# RD2166-v1_0_0.net
KiCad netlist of a schematic drawn in EAGLE
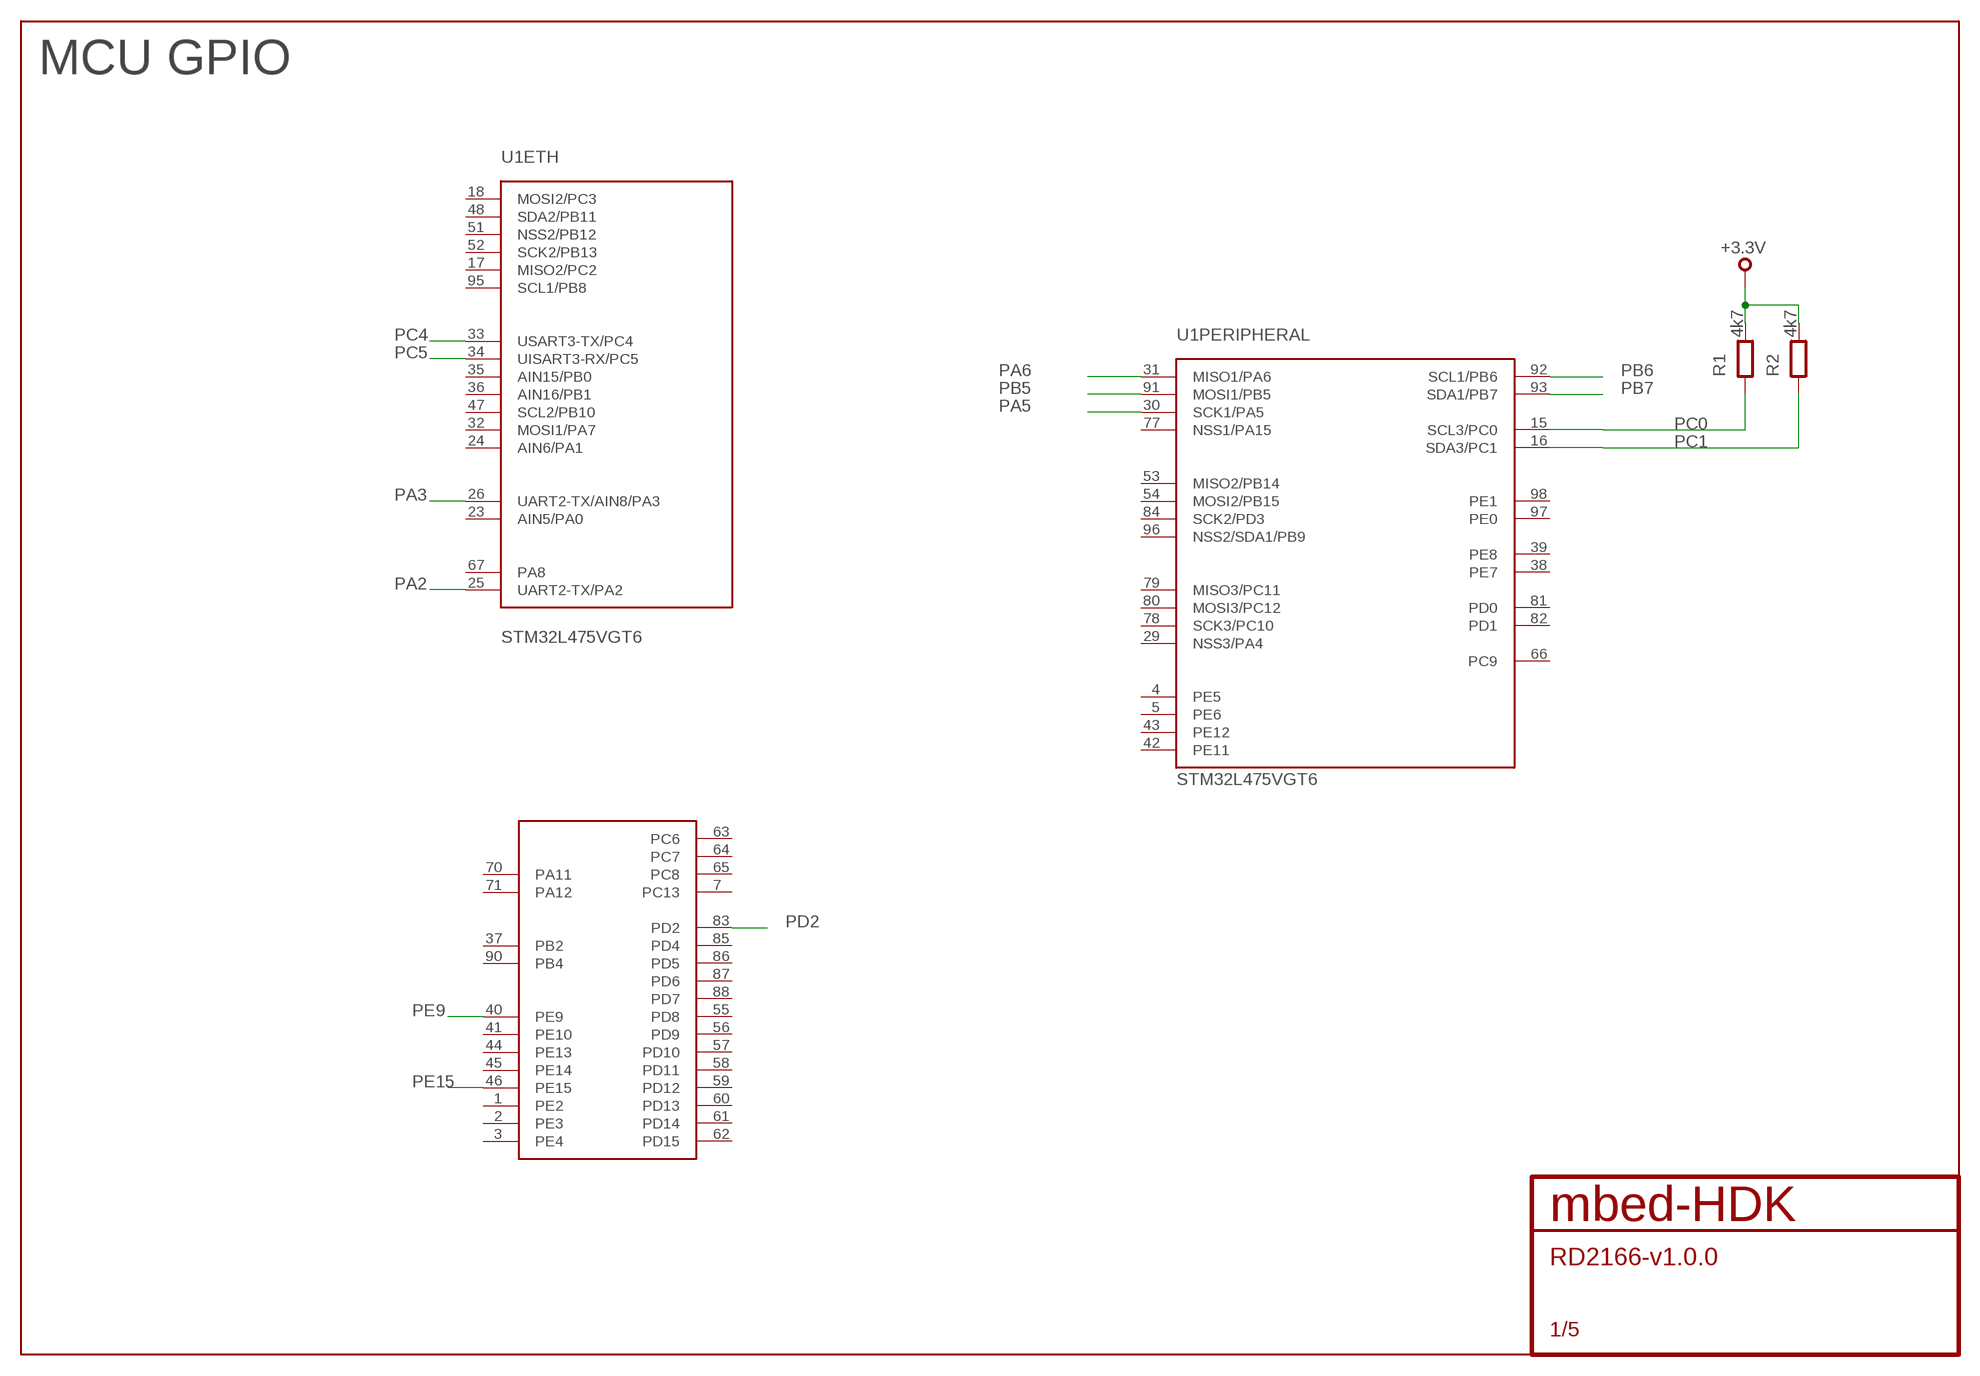
[diagram p0: schematic, sheet 1]
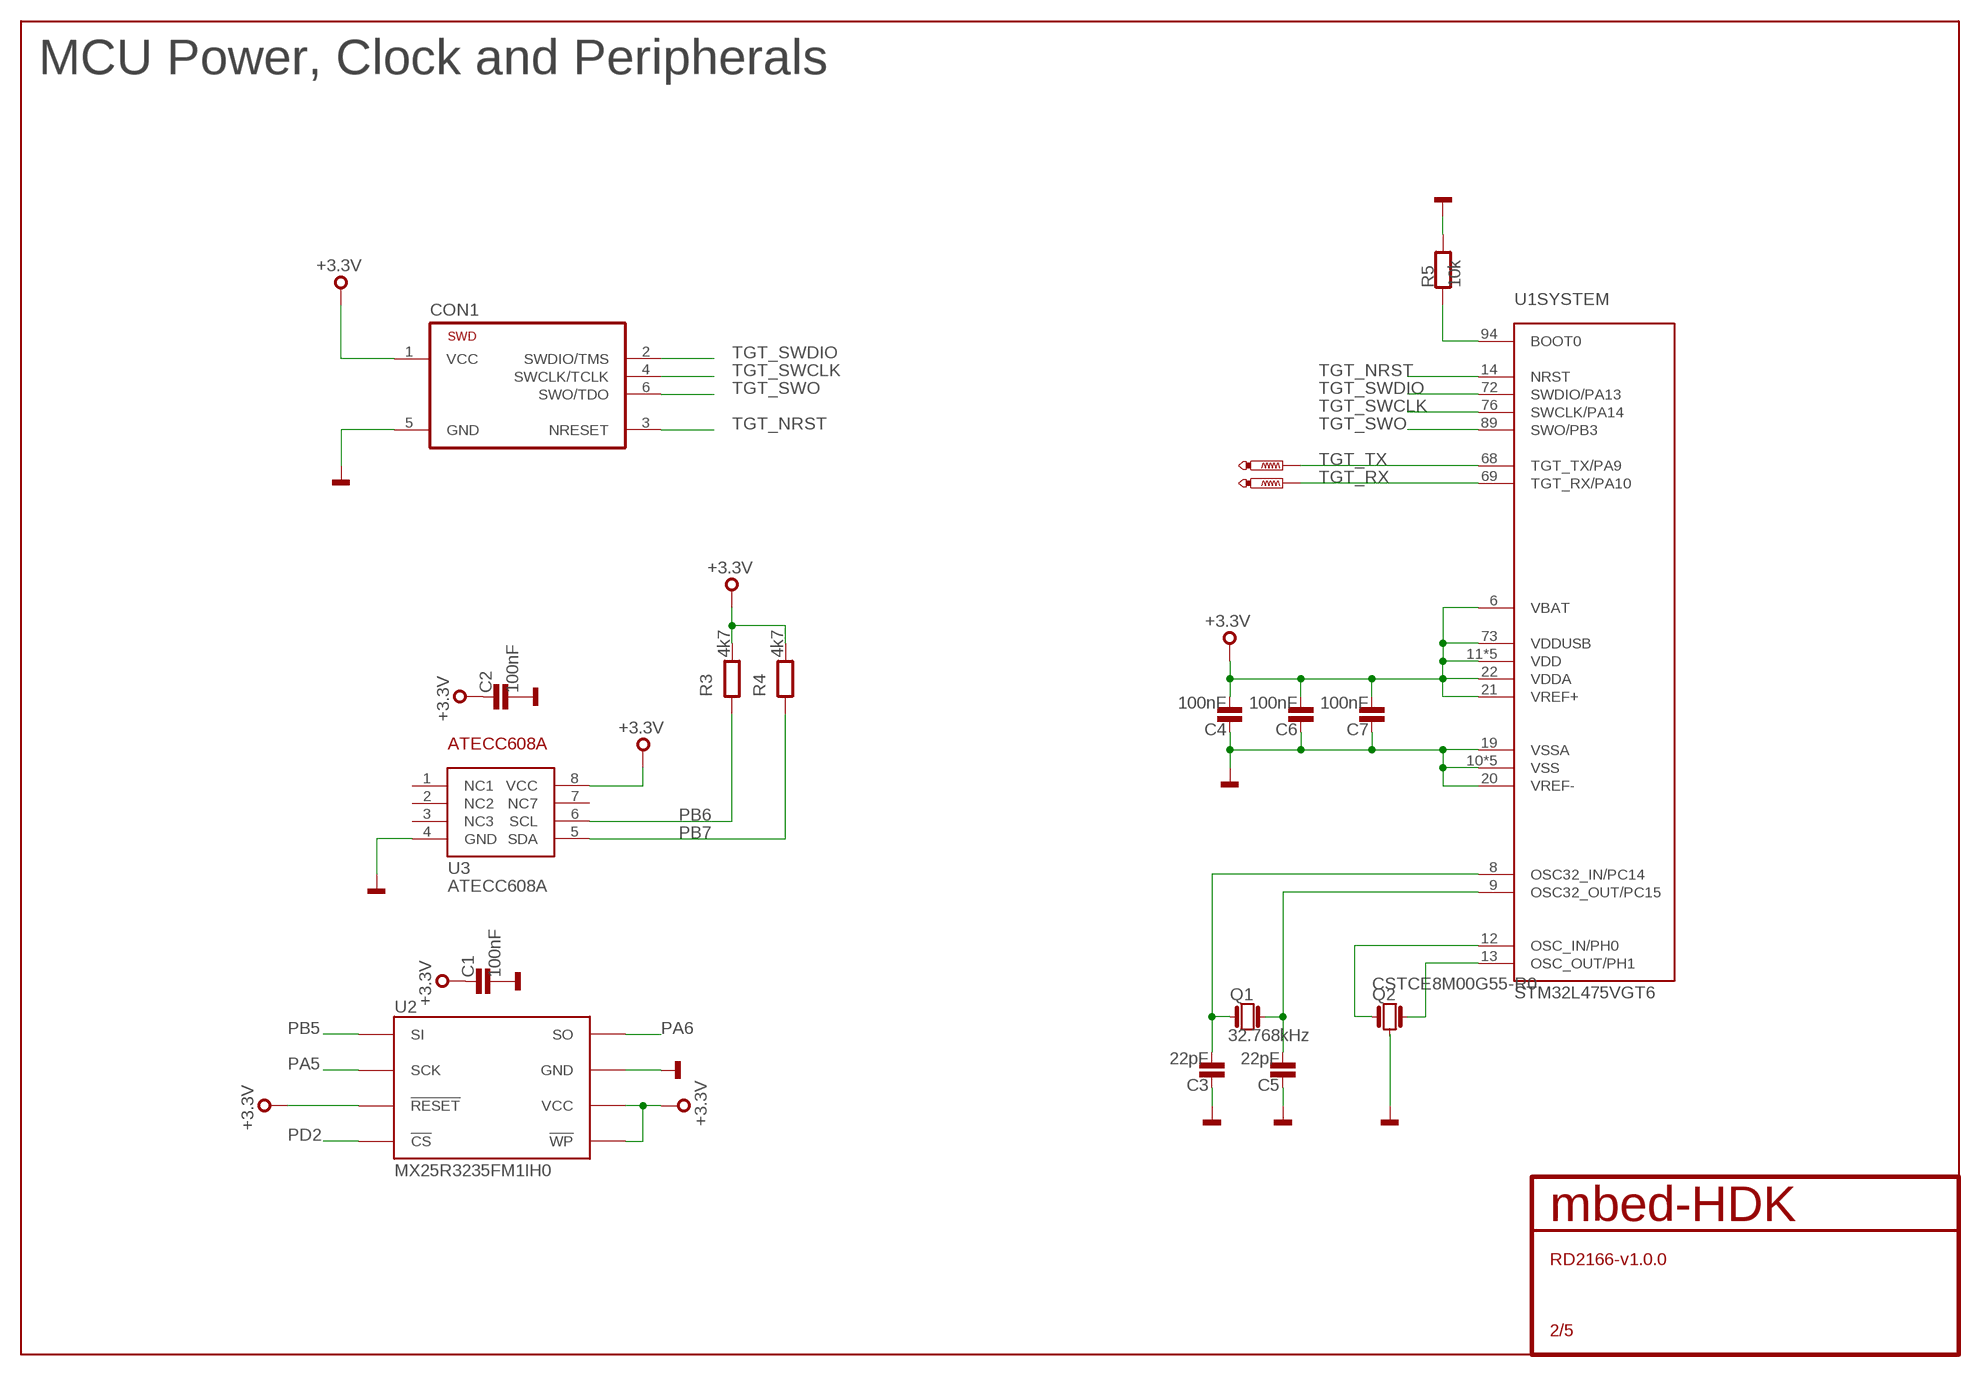
[diagram p1: schematic, sheet 2]
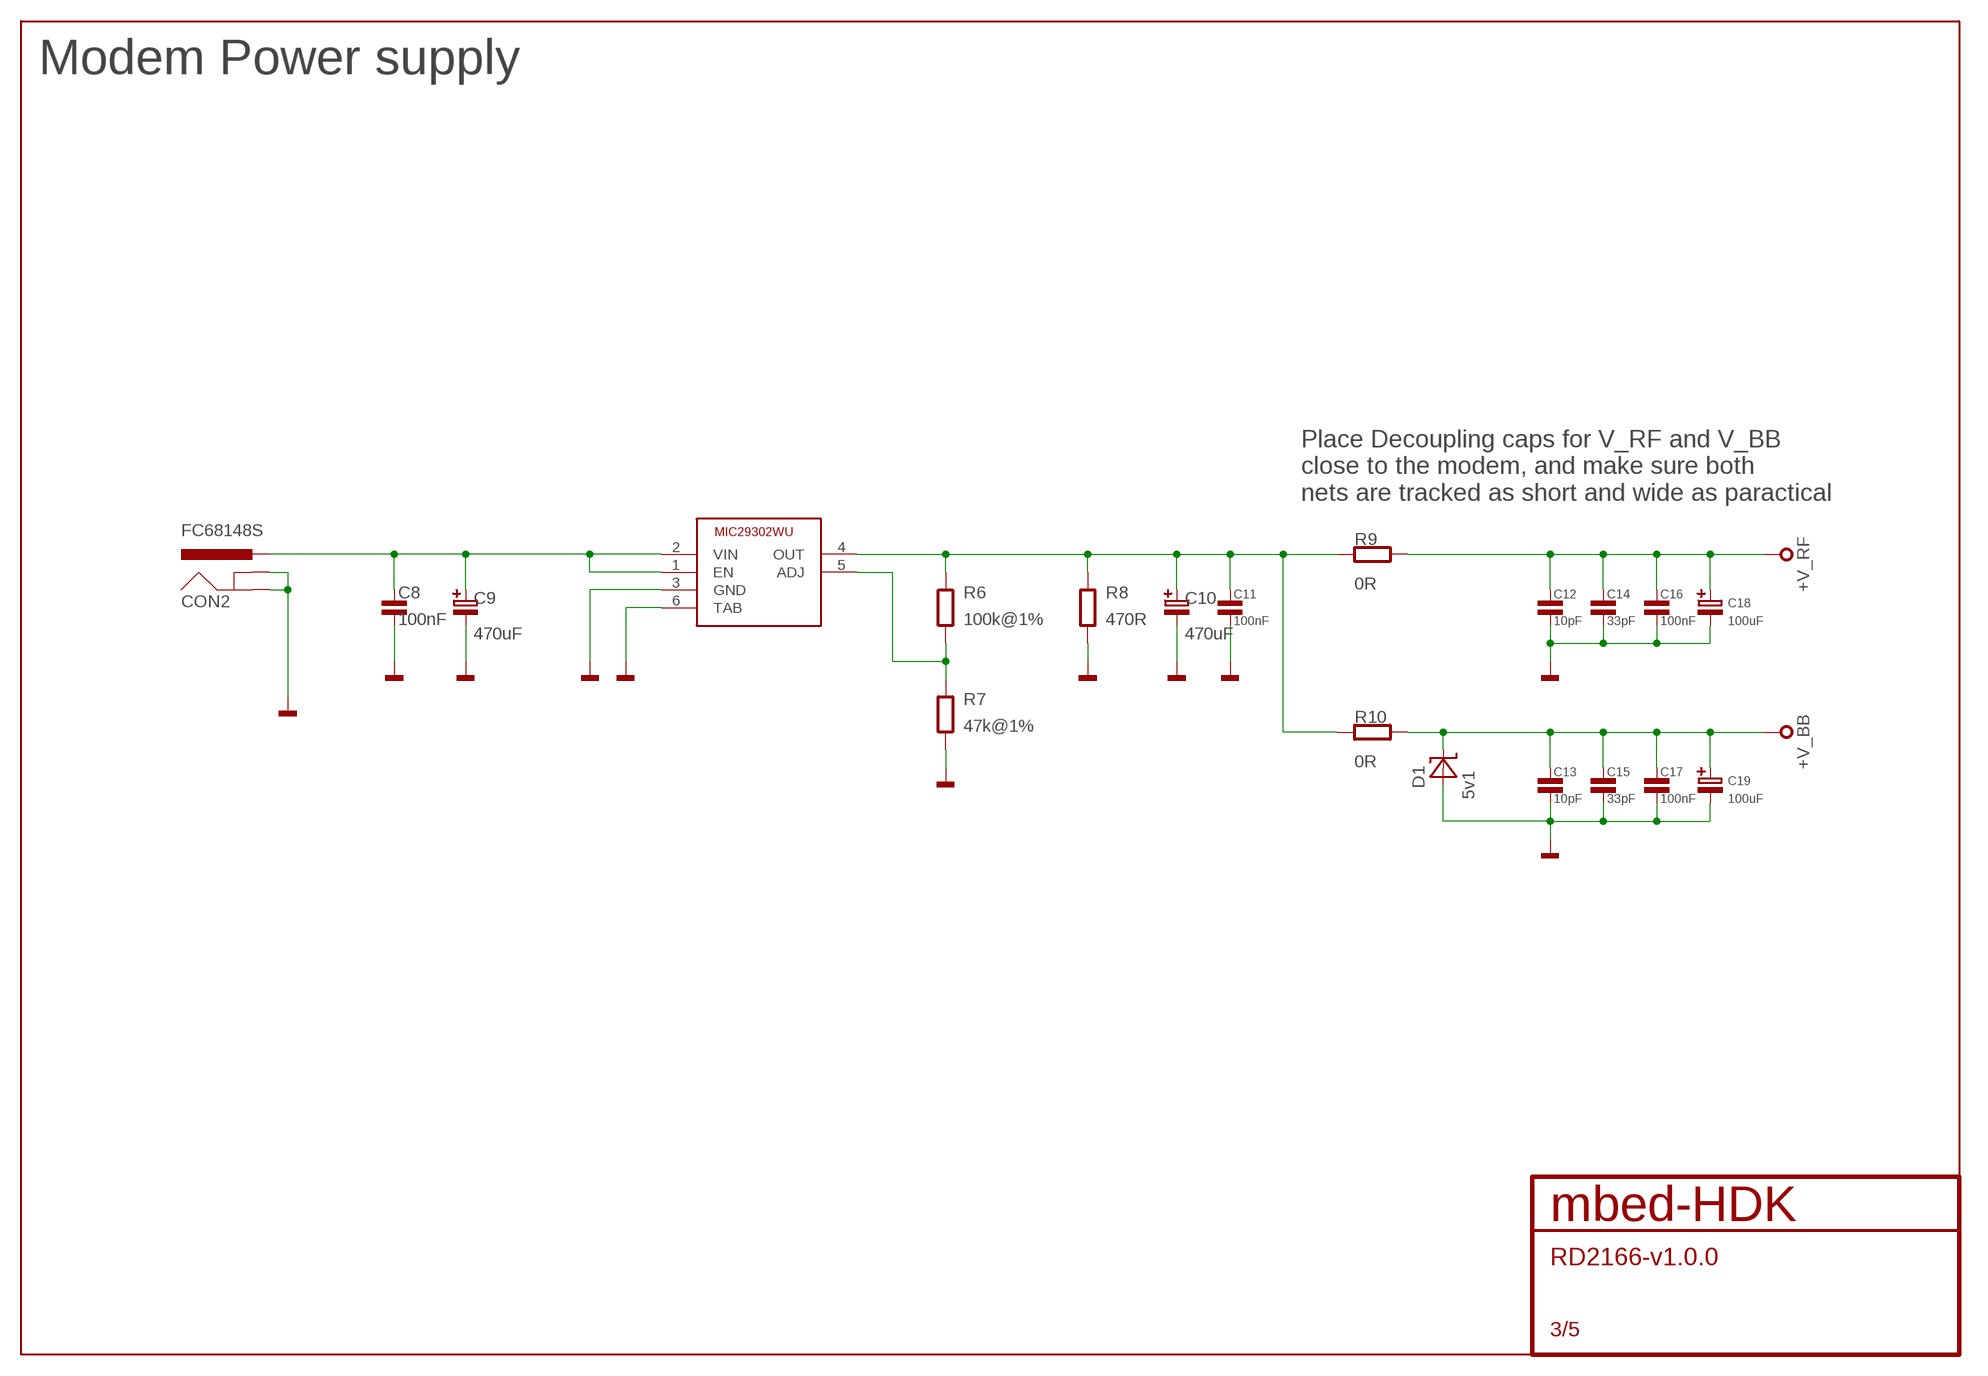
[diagram p2: schematic, sheet 3]
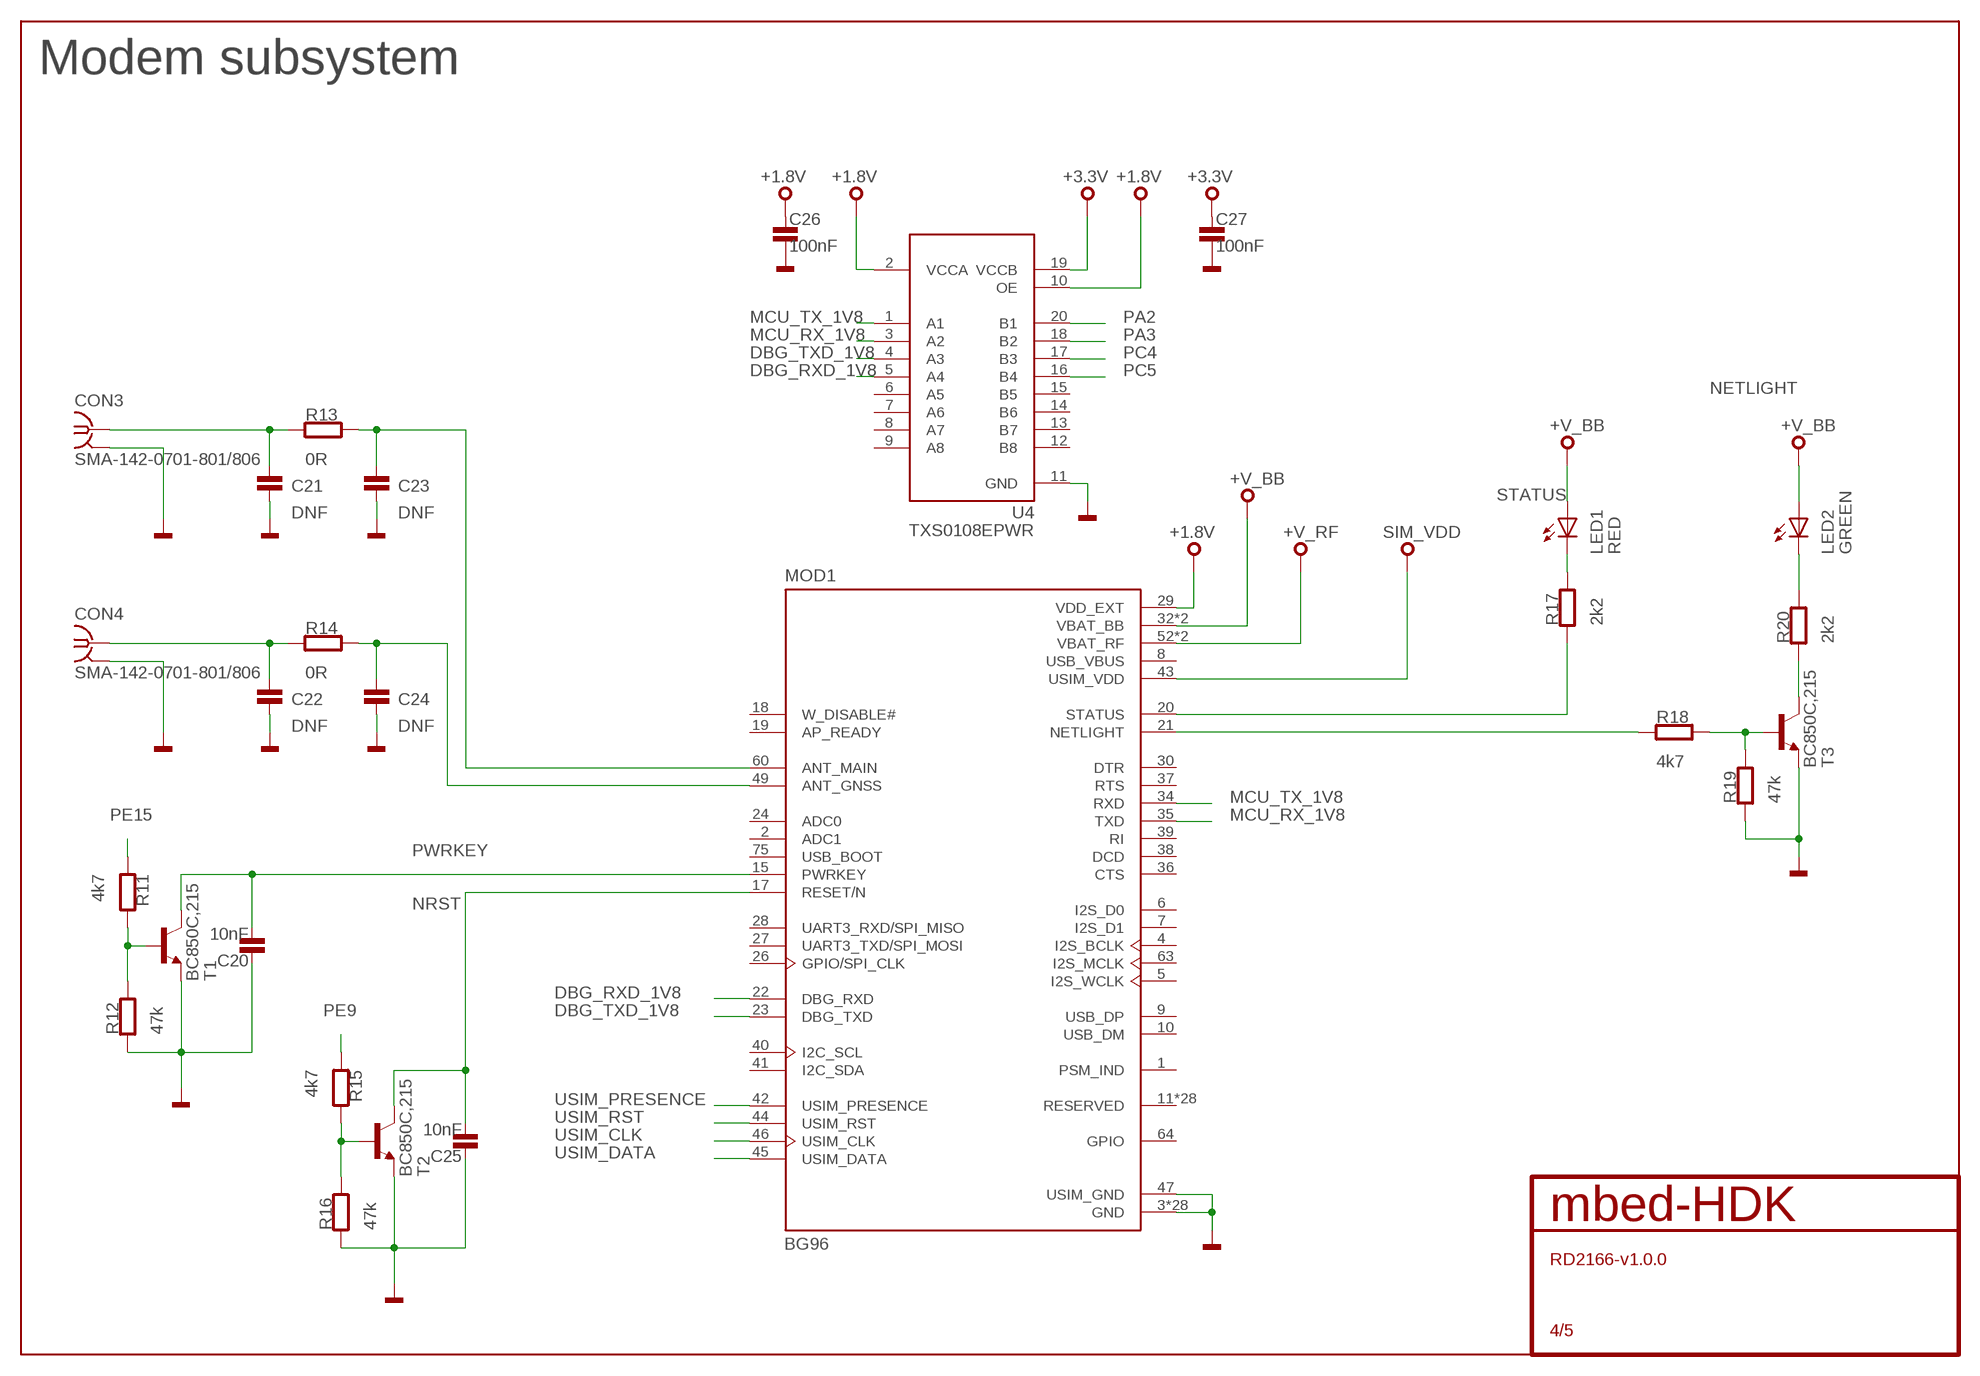
[diagram p3: schematic, sheet 4]
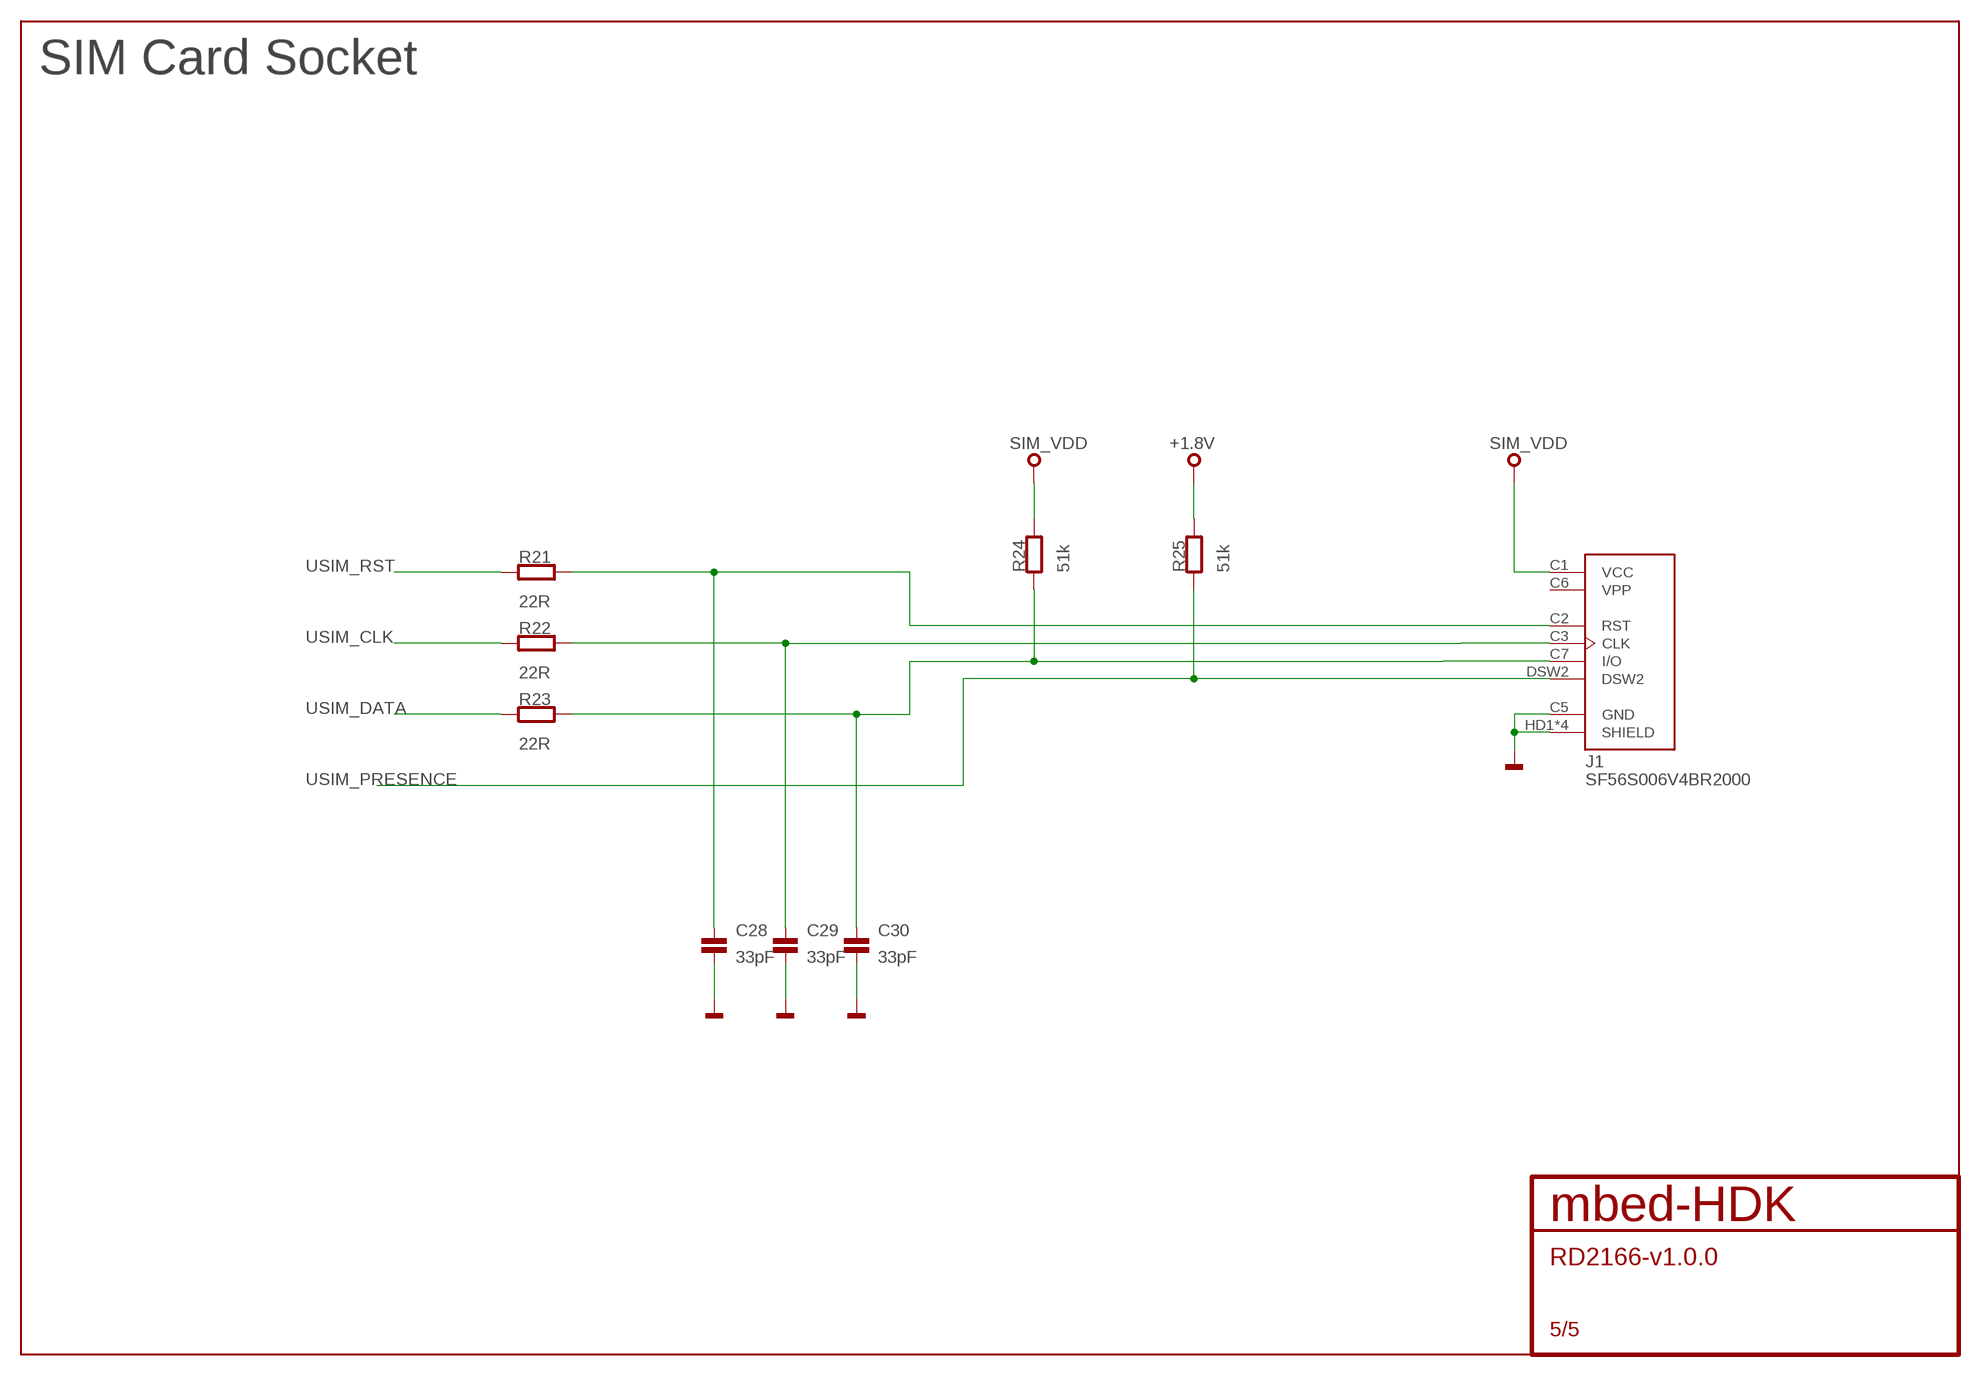
[diagram p4: schematic, sheet 5]

(export (version "E")
  (design (tool "Eeschema 10.0.6"))
  (components
    (comp (ref "C28")
      (value "33pF")
      (footprint "eagle-import:0603")
      (libsource (lib "eagle-import") (part "C0603"))
    )
    (comp (ref "C29")
      (value "33pF")
      (footprint "eagle-import:0603")
      (libsource (lib "eagle-import") (part "C0603"))
    )
    (comp (ref "C30")
      (value "33pF")
      (footprint "eagle-import:0603")
      (libsource (lib "eagle-import") (part "C0603"))
    )
    (comp (ref "J1")
      (value "SF56S006V4BR2000")
      (footprint "eagle-import:JAE_SF56S006V4BR2000")
      (fields (field (name "DIGI-KEY_PART_NUMBER") "670-2834-1-ND") (field (name "MF") "JAE Electronics"))
      (libsource (lib "eagle-import") (part "SF56S006V4BR2000"))
    )
    (comp (ref "R21")
      (value "22R")
      (footprint "eagle-import:0603")
      (libsource (lib "eagle-import") (part "R0603"))
    )
    (comp (ref "R22")
      (value "22R")
      (footprint "eagle-import:0603")
      (libsource (lib "eagle-import") (part "R0603"))
    )
    (comp (ref "R23")
      (value "22R")
      (footprint "eagle-import:0603")
      (libsource (lib "eagle-import") (part "R0603"))
    )
    (comp (ref "R24")
      (value "51k")
      (footprint "eagle-import:0603")
      (libsource (lib "eagle-import") (part "R0603"))
    )
    (comp (ref "R25")
      (value "51k")
      (footprint "eagle-import:0603")
      (libsource (lib "eagle-import") (part "R0603"))
    )
    (comp (ref "C20")
      (value "10nF")
      (footprint "eagle-import:0603")
      (libsource (lib "eagle-import") (part "C0603"))
    )
    (comp (ref "C21")
      (value "DNF")
      (footprint "eagle-import:0603")
      (libsource (lib "eagle-import") (part "C0603"))
    )
    (comp (ref "C22")
      (value "DNF")
      (footprint "eagle-import:0603")
      (libsource (lib "eagle-import") (part "C0603"))
    )
    (comp (ref "C23")
      (value "DNF")
      (footprint "eagle-import:0603")
      (libsource (lib "eagle-import") (part "C0603"))
    )
    (comp (ref "C24")
      (value "DNF")
      (footprint "eagle-import:0603")
      (libsource (lib "eagle-import") (part "C0603"))
    )
    (comp (ref "C25")
      (value "10nF")
      (footprint "eagle-import:0603")
      (libsource (lib "eagle-import") (part "C0603"))
    )
    (comp (ref "C26")
      (value "100nF")
      (footprint "eagle-import:0603")
      (libsource (lib "eagle-import") (part "C0603"))
    )
    (comp (ref "C27")
      (value "100nF")
      (footprint "eagle-import:0603")
      (libsource (lib "eagle-import") (part "C0603"))
    )
    (comp (ref "CON3")
      (value "SMA-142-0701-801/806")
      (footprint "eagle-import:J502-ND-142-0701-801_806")
      (fields (field (name "MF") "JOHNSON COMPONENTS") (field (name "MPN") "142-0701-801"))
      (libsource (lib "eagle-import") (part "SMA-142-0701-801/806"))
    )
    (comp (ref "CON4")
      (value "SMA-142-0701-801/806")
      (footprint "eagle-import:J502-ND-142-0701-801_806")
      (fields (field (name "MF") "JOHNSON COMPONENTS") (field (name "MPN") "142-0701-801"))
      (libsource (lib "eagle-import") (part "SMA-142-0701-801/806"))
    )
    (comp (ref "LED1")
      (value "RED")
      (footprint "eagle-import:CHIPLED_0603")
      (libsource (lib "eagle-import") (part "LED0603"))
    )
    (comp (ref "LED2")
      (value "GREEN")
      (footprint "eagle-import:CHIPLED_0603")
      (libsource (lib "eagle-import") (part "LED0603"))
    )
    (comp (ref "MOD1")
      (value "BG96")
      (footprint "eagle-import:LTE_MODULE_BG96")
      (fields (field (name "MF") "Quectel"))
      (libsource (lib "eagle-import") (part "BG96"))
    )
    (comp (ref "R11")
      (value "4k7")
      (footprint "eagle-import:0603")
      (libsource (lib "eagle-import") (part "R0603"))
    )
    (comp (ref "R12")
      (value "47k")
      (footprint "eagle-import:0603")
      (libsource (lib "eagle-import") (part "R0603"))
    )
    (comp (ref "R13")
      (value "0R")
      (footprint "eagle-import:0603")
      (libsource (lib "eagle-import") (part "R0603"))
    )
    (comp (ref "R14")
      (value "0R")
      (footprint "eagle-import:0603")
      (libsource (lib "eagle-import") (part "R0603"))
    )
    (comp (ref "R15")
      (value "4k7")
      (footprint "eagle-import:0603")
      (libsource (lib "eagle-import") (part "R0603"))
    )
    (comp (ref "R16")
      (value "47k")
      (footprint "eagle-import:0603")
      (libsource (lib "eagle-import") (part "R0603"))
    )
    (comp (ref "R17")
      (value "2k2")
      (footprint "eagle-import:0603")
      (libsource (lib "eagle-import") (part "R0603"))
    )
    (comp (ref "R18")
      (value "4k7")
      (footprint "eagle-import:0603")
      (libsource (lib "eagle-import") (part "R0603"))
    )
    (comp (ref "R19")
      (value "47k")
      (footprint "eagle-import:0603")
      (libsource (lib "eagle-import") (part "R0603"))
    )
    (comp (ref "R20")
      (value "2k2")
      (footprint "eagle-import:0603")
      (libsource (lib "eagle-import") (part "R0603"))
    )
    (comp (ref "T1")
      (value "BC850C,215")
      (footprint "eagle-import:SOT23-3")
      (fields (field (name "MF") "NXP Semiconductors"))
      (libsource (lib "eagle-import") (part "BC850C,215"))
    )
    (comp (ref "T2")
      (value "BC850C,215")
      (footprint "eagle-import:SOT23-3")
      (fields (field (name "MF") "NXP Semiconductors"))
      (libsource (lib "eagle-import") (part "BC850C,215"))
    )
    (comp (ref "T3")
      (value "BC850C,215")
      (footprint "eagle-import:SOT23-3")
      (fields (field (name "MF") "NXP Semiconductors"))
      (libsource (lib "eagle-import") (part "BC850C,215"))
    )
    (comp (ref "U4")
      (value "TXS0108EPWR")
      (footprint "eagle-import:TSSOP-20")
      (fields (field (name "MF") "Texas Instruments"))
      (libsource (lib "eagle-import") (part "TXS0108EPWR"))
    )
    (comp (ref "R1")
      (value "4k7")
      (footprint "eagle-import:0603")
      (libsource (lib "eagle-import") (part "R0603"))
    )
    (comp (ref "R2")
      (value "4k7")
      (footprint "eagle-import:0603")
      (libsource (lib "eagle-import") (part "R0603"))
    )
    (comp (ref "U1")
      (value "STM32L475VGT6")
      (footprint "eagle-import:QFP50P1600X1600X160-100N")
      (libsource (lib "eagle-import") (part "STM32L475VGT6"))
    )
    (comp (ref "C8")
      (value "100nF")
      (footprint "eagle-import:0603")
      (libsource (lib "eagle-import") (part "C0603"))
    )
    (comp (ref "C9")
      (value "470uF")
      (footprint "eagle-import:PANASONIC_G")
      (libsource (lib "eagle-import") (part "C-POL_G"))
    )
    (comp (ref "C10")
      (value "470uF")
      (footprint "eagle-import:PANASONIC_G")
      (libsource (lib "eagle-import") (part "C-POL_G"))
    )
    (comp (ref "C11")
      (value "100nF")
      (footprint "eagle-import:0603")
      (libsource (lib "eagle-import") (part "C0603"))
    )
    (comp (ref "C12")
      (value "10pF")
      (footprint "eagle-import:0603")
      (libsource (lib "eagle-import") (part "C0603"))
    )
    (comp (ref "C13")
      (value "10pF")
      (footprint "eagle-import:0603")
      (libsource (lib "eagle-import") (part "C0603"))
    )
    (comp (ref "C14")
      (value "33pF")
      (footprint "eagle-import:0603")
      (libsource (lib "eagle-import") (part "C0603"))
    )
    (comp (ref "C15")
      (value "33pF")
      (footprint "eagle-import:0603")
      (libsource (lib "eagle-import") (part "C0603"))
    )
    (comp (ref "C16")
      (value "100nF")
      (footprint "eagle-import:0603")
      (libsource (lib "eagle-import") (part "C0603"))
    )
    (comp (ref "C17")
      (value "100nF")
      (footprint "eagle-import:0603")
      (libsource (lib "eagle-import") (part "C0603"))
    )
    (comp (ref "C18")
      (value "100uF")
      (footprint "eagle-import:SMC_A")
      (libsource (lib "eagle-import") (part "C-POLA"))
    )
    (comp (ref "C19")
      (value "100uF")
      (footprint "eagle-import:SMC_A")
      (libsource (lib "eagle-import") (part "C-POLA"))
    )
    (comp (ref "CON2")
      (value "FC68148S")
      (footprint "eagle-import:FC68148S")
      (fields (field (name "MF") "Cliff"))
      (libsource (lib "eagle-import") (part "FC68148S"))
    )
    (comp (ref "D1")
      (value "5v1")
      (footprint "eagle-import:SOD123")
      (libsource (lib "eagle-import") (part "DIODE-ZENER"))
    )
    (comp (ref "IC1")
      (value "MIC29302WU")
      (footprint "eagle-import:TO263-5")
      (fields (field (name "MF") "Microchip"))
      (libsource (lib "eagle-import") (part "MIC29302WU"))
    )
    (comp (ref "R6")
      (value "100k@1%")
      (footprint "eagle-import:0603")
      (libsource (lib "eagle-import") (part "R0603"))
    )
    (comp (ref "R7")
      (value "47k@1%")
      (footprint "eagle-import:0603")
      (libsource (lib "eagle-import") (part "R0603"))
    )
    (comp (ref "R8")
      (value "470R")
      (footprint "eagle-import:0603")
      (libsource (lib "eagle-import") (part "R0603"))
    )
    (comp (ref "R9")
      (value "0R")
      (footprint "eagle-import:0603")
      (libsource (lib "eagle-import") (part "R0603"))
    )
    (comp (ref "R10")
      (value "0R")
      (footprint "eagle-import:0603")
      (libsource (lib "eagle-import") (part "R0603"))
    )
    (comp (ref "C1")
      (value "100nF")
      (footprint "eagle-import:0603")
      (libsource (lib "eagle-import") (part "C0603"))
    )
    (comp (ref "C2")
      (value "100nF")
      (footprint "eagle-import:0603")
      (libsource (lib "eagle-import") (part "C0603"))
    )
    (comp (ref "C3")
      (value "22pF")
      (footprint "eagle-import:0603")
      (libsource (lib "eagle-import") (part "C0603"))
    )
    (comp (ref "C4")
      (value "100nF")
      (footprint "eagle-import:0603")
      (libsource (lib "eagle-import") (part "C0603"))
    )
    (comp (ref "C5")
      (value "22pF")
      (footprint "eagle-import:0603")
      (libsource (lib "eagle-import") (part "C0603"))
    )
    (comp (ref "C6")
      (value "100nF")
      (footprint "eagle-import:0603")
      (libsource (lib "eagle-import") (part "C0603"))
    )
    (comp (ref "C7")
      (value "100nF")
      (footprint "eagle-import:0603")
      (libsource (lib "eagle-import") (part "C0603"))
    )
    (comp (ref "CON1")
      (value "TC2030-CTX-NL")
      (footprint "eagle-import:TC2030-CTX-NL")
      (libsource (lib "eagle-import") (part "TC2030-CTX-NL"))
    )
    (comp (ref "Q1")
      (value "32.768kHz")
      (footprint "eagle-import:FC135")
      (libsource (lib "eagle-import") (part "GENERIC-CRYSTAL_FC135"))
    )
    (comp (ref "Q2")
      (value "CSTCE8M00G55-R0")
      (footprint "eagle-import:CSTCE8M00G55-R0")
      (fields (field (name "MF") "Murata"))
      (libsource (lib "eagle-import") (part "CSTCE8M00G55-R0"))
    )
    (comp (ref "R3")
      (value "4k7")
      (footprint "eagle-import:0603")
      (libsource (lib "eagle-import") (part "R0603"))
    )
    (comp (ref "R4")
      (value "4k7")
      (footprint "eagle-import:0603")
      (libsource (lib "eagle-import") (part "R0603"))
    )
    (comp (ref "R5")
      (value "10k")
      (footprint "eagle-import:0603")
      (libsource (lib "eagle-import") (part "R0603"))
    )
    (comp (ref "TP1")
      (value "PTR1TP06R")
      (footprint "eagle-import:TP06R")
      (libsource (lib "eagle-import") (part "PTR1TP06R"))
    )
    (comp (ref "TP2")
      (value "PTR1TP06R")
      (footprint "eagle-import:TP06R")
      (libsource (lib "eagle-import") (part "PTR1TP06R"))
    )
    (comp (ref "U2")
      (value "MX25R3235FM1IH0")
      (footprint "eagle-import:SO8")
      (fields (field (name "MF") "Macronix"))
      (libsource (lib "eagle-import") (part "MX25R3235FM1IH0"))
    )
    (comp (ref "U3")
      (value "ATECC608A")
      (footprint "eagle-import:SO8")
      (libsource (lib "eagle-import") (part "ATECC608A"))
    )
  )
  (nets
    (net (code "1") (name "+1.8V") (class "Default")
      (node (ref "C26") (pin "1") (pinfunction "P$1_1") (pintype "passive"))
      (node (ref "MOD1") (pin "29") (pinfunction "VDD_EXT_29") (pintype "power_in"))
      (node (ref "R25") (pin "2") (pinfunction "P$2_2") (pintype "passive"))
      (node (ref "U4") (pin "10") (pinfunction "OE_10") (pintype "bidirectional"))
      (node (ref "U4") (pin "2") (pinfunction "VCCA_2") (pintype "bidirectional"))
    )
    (net (code "2") (name "+3.3V") (class "Default")
      (node (ref "C1") (pin "1") (pinfunction "P$1_1") (pintype "passive"))
      (node (ref "C2") (pin "1") (pinfunction "P$1_1") (pintype "passive"))
      (node (ref "C27") (pin "1") (pinfunction "P$1_1") (pintype "passive"))
      (node (ref "C4") (pin "2") (pinfunction "P$2_2") (pintype "passive"))
      (node (ref "C6") (pin "2") (pinfunction "P$2_2") (pintype "passive"))
      (node (ref "C7") (pin "2") (pinfunction "P$2_2") (pintype "passive"))
      (node (ref "CON1") (pin "1") (pinfunction "VCC_1") (pintype "passive"))
      (node (ref "R1") (pin "2") (pinfunction "P$2_2") (pintype "passive"))
      (node (ref "R2") (pin "2") (pinfunction "P$2_2") (pintype "passive"))
      (node (ref "R3") (pin "2") (pinfunction "P$2_2") (pintype "passive"))
      (node (ref "R4") (pin "2") (pinfunction "P$2_2") (pintype "passive"))
      (node (ref "U1") (pin "100") (pinfunction "VDD_100") (pintype "power_in"))
      (node (ref "U1") (pin "11") (pinfunction "VDD_11") (pintype "power_in"))
      (node (ref "U1") (pin "21") (pinfunction "VREF+_21") (pintype "power_in"))
      (node (ref "U1") (pin "22") (pinfunction "VDDA_22") (pintype "power_in"))
      (node (ref "U1") (pin "28") (pinfunction "VDD_28") (pintype "power_in"))
      (node (ref "U1") (pin "50") (pinfunction "VDD_50") (pintype "power_in"))
      (node (ref "U1") (pin "6") (pinfunction "VBAT_6") (pintype "power_in"))
      (node (ref "U1") (pin "73") (pinfunction "VDDUSB_73") (pintype "power_in"))
      (node (ref "U1") (pin "75") (pinfunction "VDD_75") (pintype "power_in"))
      (node (ref "U2") (pin "3") (pinfunction "~{WP}_3") (pintype "bidirectional"))
      (node (ref "U2") (pin "7") (pinfunction "~{RESET}_7") (pintype "bidirectional"))
      (node (ref "U2") (pin "8") (pinfunction "VCC_8") (pintype "bidirectional"))
      (node (ref "U3") (pin "8") (pinfunction "VCC_8") (pintype "bidirectional"))
      (node (ref "U4") (pin "19") (pinfunction "VCCB_19") (pintype "bidirectional"))
    )
    (net (code "3") (name "+V_BB") (class "Default")
      (node (ref "C13") (pin "1") (pinfunction "P$1_1") (pintype "passive"))
      (node (ref "C15") (pin "1") (pinfunction "P$1_1") (pintype "passive"))
      (node (ref "C17") (pin "1") (pinfunction "P$1_1") (pintype "passive"))
      (node (ref "C19") (pin "+") (pinfunction "+_+") (pintype "passive"))
      (node (ref "D1") (pin "2") (pinfunction "C_2") (pintype "passive"))
      (node (ref "LED1") (pin "A") (pinfunction "A_A") (pintype "passive"))
      (node (ref "LED2") (pin "A") (pinfunction "A_A") (pintype "passive"))
      (node (ref "MOD1") (pin "32") (pinfunction "VBAT_BB_32") (pintype "power_in"))
      (node (ref "MOD1") (pin "33") (pinfunction "VBAT_BB_33") (pintype "power_in"))
      (node (ref "R10") (pin "2") (pinfunction "P$2_2") (pintype "passive"))
    )
    (net (code "4") (name "+V_RF") (class "Default")
      (node (ref "C12") (pin "1") (pinfunction "P$1_1") (pintype "passive"))
      (node (ref "C14") (pin "1") (pinfunction "P$1_1") (pintype "passive"))
      (node (ref "C16") (pin "1") (pinfunction "P$1_1") (pintype "passive"))
      (node (ref "C18") (pin "+") (pinfunction "+_+") (pintype "passive"))
      (node (ref "MOD1") (pin "52") (pinfunction "VBAT_RF_52") (pintype "power_in"))
      (node (ref "MOD1") (pin "53") (pinfunction "VBAT_RF_53") (pintype "power_in"))
      (node (ref "R9") (pin "2") (pinfunction "P$2_2") (pintype "passive"))
    )
    (net (code "5") (name "DBG_RXD_1V8") (class "Default")
      (node (ref "MOD1") (pin "22") (pinfunction "DBG_RXD_22") (pintype "input"))
      (node (ref "U4") (pin "5") (pinfunction "A4_5") (pintype "bidirectional"))
    )
    (net (code "6") (name "DBG_TXD_1V8") (class "Default")
      (node (ref "MOD1") (pin "23") (pinfunction "DBG_TXD_23") (pintype "output"))
      (node (ref "U4") (pin "4") (pinfunction "A3_4") (pintype "bidirectional"))
    )
    (net (code "7") (name "GND") (class "Default")
      (node (ref "C1") (pin "2") (pinfunction "P$2_2") (pintype "passive"))
      (node (ref "C10") (pin "-") (pinfunction "-_-") (pintype "passive"))
      (node (ref "C11") (pin "2") (pinfunction "P$2_2") (pintype "passive"))
      (node (ref "C12") (pin "2") (pinfunction "P$2_2") (pintype "passive"))
      (node (ref "C13") (pin "2") (pinfunction "P$2_2") (pintype "passive"))
      (node (ref "C14") (pin "2") (pinfunction "P$2_2") (pintype "passive"))
      (node (ref "C15") (pin "2") (pinfunction "P$2_2") (pintype "passive"))
      (node (ref "C16") (pin "2") (pinfunction "P$2_2") (pintype "passive"))
      (node (ref "C17") (pin "2") (pinfunction "P$2_2") (pintype "passive"))
      (node (ref "C18") (pin "-") (pinfunction "-_-") (pintype "passive"))
      (node (ref "C19") (pin "-") (pinfunction "-_-") (pintype "passive"))
      (node (ref "C2") (pin "2") (pinfunction "P$2_2") (pintype "passive"))
      (node (ref "C20") (pin "1") (pinfunction "P$1_1") (pintype "passive"))
      (node (ref "C21") (pin "1") (pinfunction "P$1_1") (pintype "passive"))
      (node (ref "C22") (pin "1") (pinfunction "P$1_1") (pintype "passive"))
      (node (ref "C23") (pin "1") (pinfunction "P$1_1") (pintype "passive"))
      (node (ref "C24") (pin "1") (pinfunction "P$1_1") (pintype "passive"))
      (node (ref "C25") (pin "1") (pinfunction "P$1_1") (pintype "passive"))
      (node (ref "C26") (pin "2") (pinfunction "P$2_2") (pintype "passive"))
      (node (ref "C27") (pin "2") (pinfunction "P$2_2") (pintype "passive"))
      (node (ref "C28") (pin "2") (pinfunction "P$2_2") (pintype "passive"))
      (node (ref "C29") (pin "2") (pinfunction "P$2_2") (pintype "passive"))
      (node (ref "C3") (pin "1") (pinfunction "P$1_1") (pintype "passive"))
      (node (ref "C30") (pin "2") (pinfunction "P$2_2") (pintype "passive"))
      (node (ref "C4") (pin "1") (pinfunction "P$1_1") (pintype "passive"))
      (node (ref "C5") (pin "1") (pinfunction "P$1_1") (pintype "passive"))
      (node (ref "C6") (pin "1") (pinfunction "P$1_1") (pintype "passive"))
      (node (ref "C7") (pin "1") (pinfunction "P$1_1") (pintype "passive"))
      (node (ref "C8") (pin "2") (pinfunction "P$2_2") (pintype "passive"))
      (node (ref "C9") (pin "-") (pinfunction "-_-") (pintype "passive"))
      (node (ref "CON1") (pin "5") (pinfunction "GND_5") (pintype "passive"))
      (node (ref "CON2") (pin "2") (pinfunction "GNDBREAK_2") (pintype "bidirectional"))
      (node (ref "CON2") (pin "3") (pinfunction "GND_3") (pintype "bidirectional"))
      (node (ref "CON3") (pin "G@1") (pinfunction "2_G@1") (pintype "passive"))
      (node (ref "CON3") (pin "G@2") (pinfunction "2_G@2") (pintype "passive"))
      (node (ref "CON3") (pin "G@3") (pinfunction "2_G@3") (pintype "passive"))
      (node (ref "CON3") (pin "G@4") (pinfunction "2_G@4") (pintype "passive"))
      (node (ref "CON4") (pin "G@1") (pinfunction "2_G@1") (pintype "passive"))
      (node (ref "CON4") (pin "G@2") (pinfunction "2_G@2") (pintype "passive"))
      (node (ref "CON4") (pin "G@3") (pinfunction "2_G@3") (pintype "passive"))
      (node (ref "CON4") (pin "G@4") (pinfunction "2_G@4") (pintype "passive"))
      (node (ref "D1") (pin "1") (pinfunction "A_1") (pintype "passive"))
      (node (ref "IC1") (pin "3") (pinfunction "GND_3") (pintype "bidirectional"))
      (node (ref "IC1") (pin "6") (pinfunction "TAB_6") (pintype "bidirectional"))
      (node (ref "J1") (pin "C5") (pinfunction "GND_C5") (pintype "power_in"))
      (node (ref "J1") (pin "HD1") (pinfunction "SHIELD_HD1") (pintype "power_in"))
      (node (ref "J1") (pin "HD2,DSW1") (pinfunction "SHIELD_HD2,DSW1") (pintype "power_in"))
      (node (ref "J1") (pin "HD3") (pinfunction "SHIELD_HD3") (pintype "power_in"))
      (node (ref "J1") (pin "HD4") (pinfunction "SHIELD_HD4") (pintype "power_in"))
      (node (ref "MOD1") (pin "100") (pinfunction "GND_100") (pintype "power_in"))
      (node (ref "MOD1") (pin "101") (pinfunction "GND_101") (pintype "power_in"))
      (node (ref "MOD1") (pin "102") (pinfunction "GND_102") (pintype "power_in"))
      (node (ref "MOD1") (pin "3") (pinfunction "GND_3") (pintype "power_in"))
      (node (ref "MOD1") (pin "31") (pinfunction "GND_31") (pintype "power_in"))
      (node (ref "MOD1") (pin "47") (pinfunction "USIM_GND_47") (pintype "power_in"))
      (node (ref "MOD1") (pin "48") (pinfunction "GND_48") (pintype "power_in"))
      (node (ref "MOD1") (pin "50") (pinfunction "GND_50") (pintype "power_in"))
      (node (ref "MOD1") (pin "54") (pinfunction "GND_54") (pintype "power_in"))
      (node (ref "MOD1") (pin "55") (pinfunction "GND_55") (pintype "power_in"))
      (node (ref "MOD1") (pin "58") (pinfunction "GND_58") (pintype "power_in"))
      (node (ref "MOD1") (pin "59") (pinfunction "GND_59") (pintype "power_in"))
      (node (ref "MOD1") (pin "61") (pinfunction "GND_61") (pintype "power_in"))
      (node (ref "MOD1") (pin "62") (pinfunction "GND_62") (pintype "power_in"))
      (node (ref "MOD1") (pin "67") (pinfunction "GND_67") (pintype "power_in"))
      (node (ref "MOD1") (pin "68") (pinfunction "GND_68") (pintype "power_in"))
      (node (ref "MOD1") (pin "69") (pinfunction "GND_69") (pintype "power_in"))
      (node (ref "MOD1") (pin "70") (pinfunction "GND_70") (pintype "power_in"))
      (node (ref "MOD1") (pin "71") (pinfunction "GND_71") (pintype "power_in"))
      (node (ref "MOD1") (pin "72") (pinfunction "GND_72") (pintype "power_in"))
      (node (ref "MOD1") (pin "73") (pinfunction "GND_73") (pintype "power_in"))
      (node (ref "MOD1") (pin "74") (pinfunction "GND_74") (pintype "power_in"))
      (node (ref "MOD1") (pin "79") (pinfunction "GND_79") (pintype "power_in"))
      (node (ref "MOD1") (pin "80") (pinfunction "GND_80") (pintype "power_in"))
      (node (ref "MOD1") (pin "81") (pinfunction "GND_81") (pintype "power_in"))
      (node (ref "MOD1") (pin "82") (pinfunction "GND_82") (pintype "power_in"))
      (node (ref "MOD1") (pin "89") (pinfunction "GND_89") (pintype "power_in"))
      (node (ref "MOD1") (pin "90") (pinfunction "GND_90") (pintype "power_in"))
      (node (ref "MOD1") (pin "91") (pinfunction "GND_91") (pintype "power_in"))
      (node (ref "Q2") (pin "2") (pinfunction "2_2") (pintype "passive"))
      (node (ref "R12") (pin "1") (pinfunction "P$1_1") (pintype "passive"))
      (node (ref "R16") (pin "1") (pinfunction "P$1_1") (pintype "passive"))
      (node (ref "R19") (pin "1") (pinfunction "P$1_1") (pintype "passive"))
      (node (ref "R5") (pin "2") (pinfunction "P$2_2") (pintype "passive"))
      (node (ref "R7") (pin "1") (pinfunction "P$1_1") (pintype "passive"))
      (node (ref "R8") (pin "1") (pinfunction "P$1_1") (pintype "passive"))
      (node (ref "T1") (pin "2") (pinfunction "E_2") (pintype "passive"))
      (node (ref "T2") (pin "2") (pinfunction "E_2") (pintype "passive"))
      (node (ref "T3") (pin "2") (pinfunction "E_2") (pintype "passive"))
      (node (ref "U1") (pin "10") (pinfunction "VSS_10") (pintype "power_in"))
      (node (ref "U1") (pin "19") (pinfunction "VSSA_19") (pintype "power_in"))
      (node (ref "U1") (pin "20") (pinfunction "VREF-_20") (pintype "power_in"))
      (node (ref "U1") (pin "27") (pinfunction "VSS_27") (pintype "power_in"))
      (node (ref "U1") (pin "49") (pinfunction "VSS_49") (pintype "power_in"))
      (node (ref "U1") (pin "74") (pinfunction "VSS_74") (pintype "power_in"))
      (node (ref "U1") (pin "99") (pinfunction "VSS_99") (pintype "power_in"))
      (node (ref "U2") (pin "4") (pinfunction "GND_4") (pintype "bidirectional"))
      (node (ref "U3") (pin "4") (pinfunction "GND_4") (pintype "bidirectional"))
      (node (ref "U4") (pin "11") (pinfunction "GND_11") (pintype "bidirectional"))
    )
    (net (code "8") (name "MCU_RX_1V8") (class "Default")
      (node (ref "MOD1") (pin "35") (pinfunction "TXD_35") (pintype "output"))
      (node (ref "U4") (pin "3") (pinfunction "A2_3") (pintype "bidirectional"))
    )
    (net (code "9") (name "MCU_TX_1V8") (class "Default")
      (node (ref "MOD1") (pin "34") (pinfunction "RXD_34") (pintype "input"))
      (node (ref "U4") (pin "1") (pinfunction "A1_1") (pintype "bidirectional"))
    )
    (net (code "10") (name "NETLIGHT") (class "Default")
      (node (ref "MOD1") (pin "21") (pinfunction "NETLIGHT_21") (pintype "output"))
      (node (ref "R18") (pin "1") (pinfunction "P$1_1") (pintype "passive"))
    )
    (net (code "11") (name "NRST") (class "Default")
      (node (ref "C25") (pin "2") (pinfunction "P$2_2") (pintype "passive"))
      (node (ref "MOD1") (pin "17") (pinfunction "RESET/N_17") (pintype "input"))
      (node (ref "T2") (pin "3") (pinfunction "C_3") (pintype "passive"))
    )
    (net (code "12") (name "Net-(C3-P$2)") (class "Default")
      (node (ref "C3") (pin "2") (pinfunction "P$2_2") (pintype "passive"))
      (node (ref "Q1") (pin "X1") (pinfunction "1_X1") (pintype "passive"))
      (node (ref "U1") (pin "8") (pinfunction "OSC32_IN/PC14_8") (pintype "bidirectional"))
    )
    (net (code "13") (name "Net-(C5-P$2)") (class "Default")
      (node (ref "C5") (pin "2") (pinfunction "P$2_2") (pintype "passive"))
      (node (ref "Q1") (pin "X2") (pinfunction "2_X2") (pintype "passive"))
      (node (ref "U1") (pin "9") (pinfunction "OSC32_OUT/PC15_9") (pintype "bidirectional"))
    )
    (net (code "14") (name "Net-(C8-P$1)") (class "Default")
      (node (ref "C8") (pin "1") (pinfunction "P$1_1") (pintype "passive"))
      (node (ref "C9") (pin "+") (pinfunction "+_+") (pintype "passive"))
      (node (ref "CON2") (pin "1-1") (pinfunction "PWR_1-1") (pintype "bidirectional"))
      (node (ref "CON2") (pin "1-2") (pinfunction "PWR_1-2") (pintype "bidirectional"))
      (node (ref "IC1") (pin "1") (pinfunction "EN_1") (pintype "bidirectional"))
      (node (ref "IC1") (pin "2") (pinfunction "VIN_2") (pintype "bidirectional"))
    )
    (net (code "15") (name "Net-(C11-P$1)") (class "Default")
      (node (ref "C10") (pin "+") (pinfunction "+_+") (pintype "passive"))
      (node (ref "C11") (pin "1") (pinfunction "P$1_1") (pintype "passive"))
      (node (ref "IC1") (pin "4") (pinfunction "OUT_4") (pintype "bidirectional"))
      (node (ref "R10") (pin "1") (pinfunction "P$1_1") (pintype "passive"))
      (node (ref "R6") (pin "2") (pinfunction "P$2_2") (pintype "passive"))
      (node (ref "R8") (pin "2") (pinfunction "P$2_2") (pintype "passive"))
      (node (ref "R9") (pin "1") (pinfunction "P$1_1") (pintype "passive"))
    )
    (net (code "16") (name "Net-(C21-P$2)") (class "Default")
      (node (ref "C21") (pin "2") (pinfunction "P$2_2") (pintype "passive"))
      (node (ref "CON3") (pin "1") (pinfunction "1_1") (pintype "passive"))
      (node (ref "R13") (pin "1") (pinfunction "P$1_1") (pintype "passive"))
    )
    (net (code "17") (name "Net-(C22-P$2)") (class "Default")
      (node (ref "C22") (pin "2") (pinfunction "P$2_2") (pintype "passive"))
      (node (ref "CON4") (pin "1") (pinfunction "1_1") (pintype "passive"))
      (node (ref "R14") (pin "1") (pinfunction "P$1_1") (pintype "passive"))
    )
    (net (code "18") (name "Net-(C23-P$2)") (class "Default")
      (node (ref "C23") (pin "2") (pinfunction "P$2_2") (pintype "passive"))
      (node (ref "MOD1") (pin "60") (pinfunction "ANT_MAIN_60") (pintype "bidirectional"))
      (node (ref "R13") (pin "2") (pinfunction "P$2_2") (pintype "passive"))
    )
    (net (code "19") (name "Net-(C24-P$2)") (class "Default")
      (node (ref "C24") (pin "2") (pinfunction "P$2_2") (pintype "passive"))
      (node (ref "MOD1") (pin "49") (pinfunction "ANT_GNSS_49") (pintype "input"))
      (node (ref "R14") (pin "2") (pinfunction "P$2_2") (pintype "passive"))
    )
    (net (code "20") (name "Net-(C28-P$1)") (class "Default")
      (node (ref "C28") (pin "1") (pinfunction "P$1_1") (pintype "passive"))
      (node (ref "J1") (pin "C2") (pinfunction "RST_C2") (pintype "input"))
      (node (ref "R21") (pin "2") (pinfunction "P$2_2") (pintype "passive"))
    )
    (net (code "21") (name "Net-(C29-P$1)") (class "Default")
      (node (ref "C29") (pin "1") (pinfunction "P$1_1") (pintype "passive"))
      (node (ref "J1") (pin "C3") (pinfunction "CLK_C3") (pintype "input"))
      (node (ref "R22") (pin "2") (pinfunction "P$2_2") (pintype "passive"))
    )
    (net (code "22") (name "Net-(C30-P$1)") (class "Default")
      (node (ref "C30") (pin "1") (pinfunction "P$1_1") (pintype "passive"))
      (node (ref "J1") (pin "C7") (pinfunction "I/O_C7") (pintype "bidirectional"))
      (node (ref "R23") (pin "2") (pinfunction "P$2_2") (pintype "passive"))
      (node (ref "R24") (pin "1") (pinfunction "P$1_1") (pintype "passive"))
    )
    (net (code "23") (name "Net-(IC1-ADJ)") (class "Default")
      (node (ref "IC1") (pin "5") (pinfunction "ADJ_5") (pintype "bidirectional"))
      (node (ref "R6") (pin "1") (pinfunction "P$1_1") (pintype "passive"))
      (node (ref "R7") (pin "2") (pinfunction "P$2_2") (pintype "passive"))
    )
    (net (code "24") (name "Net-(R5-P$1)") (class "Default")
      (node (ref "R5") (pin "1") (pinfunction "P$1_1") (pintype "passive"))
      (node (ref "U1") (pin "94") (pinfunction "BOOT0_94") (pintype "input"))
    )
    (net (code "25") (name "Net-(R11-P$2)") (class "Default")
      (node (ref "R11") (pin "2") (pinfunction "P$2_2") (pintype "passive"))
      (node (ref "R12") (pin "2") (pinfunction "P$2_2") (pintype "passive"))
      (node (ref "T1") (pin "1") (pinfunction "B_1") (pintype "passive"))
    )
    (net (code "26") (name "Net-(R15-P$2)") (class "Default")
      (node (ref "R15") (pin "2") (pinfunction "P$2_2") (pintype "passive"))
      (node (ref "R16") (pin "2") (pinfunction "P$2_2") (pintype "passive"))
      (node (ref "T2") (pin "1") (pinfunction "B_1") (pintype "passive"))
    )
    (net (code "27") (name "Net-(R17-P$2)") (class "Default")
      (node (ref "LED1") (pin "C") (pinfunction "C_C") (pintype "passive"))
      (node (ref "R17") (pin "2") (pinfunction "P$2_2") (pintype "passive"))
    )
    (net (code "28") (name "Net-(R18-P$2)") (class "Default")
      (node (ref "R18") (pin "2") (pinfunction "P$2_2") (pintype "passive"))
      (node (ref "R19") (pin "2") (pinfunction "P$2_2") (pintype "passive"))
      (node (ref "T3") (pin "1") (pinfunction "B_1") (pintype "passive"))
    )
    (net (code "29") (name "Net-(R20-P$1)") (class "Default")
      (node (ref "R20") (pin "1") (pinfunction "P$1_1") (pintype "passive"))
      (node (ref "T3") (pin "3") (pinfunction "C_3") (pintype "passive"))
    )
    (net (code "30") (name "Net-(R20-P$2)") (class "Default")
      (node (ref "LED2") (pin "C") (pinfunction "C_C") (pintype "passive"))
      (node (ref "R20") (pin "2") (pinfunction "P$2_2") (pintype "passive"))
    )
    (net (code "31") (name "Net-(U1D-OSC_IN{slash}PH0)") (class "Default")
      (node (ref "Q2") (pin "1") (pinfunction "1_1") (pintype "passive"))
      (node (ref "U1") (pin "12") (pinfunction "OSC_IN/PH0_12") (pintype "bidirectional"))
    )
    (net (code "32") (name "Net-(U1D-OSC_OUT{slash}PH1)") (class "Default")
      (node (ref "Q2") (pin "3") (pinfunction "3_3") (pintype "passive"))
      (node (ref "U1") (pin "13") (pinfunction "OSC_OUT/PH1_13") (pintype "bidirectional"))
    )
    (net (code "33") (name "PA2") (class "Default")
      (node (ref "U1") (pin "25") (pinfunction "UART2-TX/PA2_25") (pintype "bidirectional"))
      (node (ref "U4") (pin "20") (pinfunction "B1_20") (pintype "bidirectional"))
    )
    (net (code "34") (name "PA3") (class "Default")
      (node (ref "U1") (pin "26") (pinfunction "UART2-TX/AIN8/PA3_26") (pintype "bidirectional"))
      (node (ref "U4") (pin "18") (pinfunction "B2_18") (pintype "bidirectional"))
    )
    (net (code "35") (name "PA5") (class "Default")
      (node (ref "U1") (pin "30") (pinfunction "SCK1/PA5_30") (pintype "bidirectional"))
      (node (ref "U2") (pin "6") (pinfunction "SCK_6") (pintype "bidirectional"))
    )
    (net (code "36") (name "PA6") (class "Default")
      (node (ref "U1") (pin "31") (pinfunction "MISO1/PA6_31") (pintype "bidirectional"))
      (node (ref "U2") (pin "2") (pinfunction "SO_2") (pintype "bidirectional"))
    )
    (net (code "37") (name "PB5") (class "Default")
      (node (ref "U1") (pin "91") (pinfunction "MOSI1/PB5_91") (pintype "bidirectional"))
      (node (ref "U2") (pin "5") (pinfunction "SI_5") (pintype "bidirectional"))
    )
    (net (code "38") (name "PB6") (class "Default")
      (node (ref "R3") (pin "1") (pinfunction "P$1_1") (pintype "passive"))
      (node (ref "U1") (pin "92") (pinfunction "SCL1/PB6_92") (pintype "bidirectional"))
      (node (ref "U3") (pin "6") (pinfunction "SCL_6") (pintype "bidirectional"))
    )
    (net (code "39") (name "PB7") (class "Default")
      (node (ref "R4") (pin "1") (pinfunction "P$1_1") (pintype "passive"))
      (node (ref "U1") (pin "93") (pinfunction "SDA1/PB7_93") (pintype "bidirectional"))
      (node (ref "U3") (pin "5") (pinfunction "SDA_5") (pintype "bidirectional"))
    )
    (net (code "40") (name "PC0") (class "Default")
      (node (ref "R1") (pin "1") (pinfunction "P$1_1") (pintype "passive"))
      (node (ref "U1") (pin "15") (pinfunction "SCL3/PC0_15") (pintype "bidirectional"))
    )
    (net (code "41") (name "PC1") (class "Default")
      (node (ref "R2") (pin "1") (pinfunction "P$1_1") (pintype "passive"))
      (node (ref "U1") (pin "16") (pinfunction "SDA3/PC1_16") (pintype "bidirectional"))
    )
    (net (code "42") (name "PC4") (class "Default")
      (node (ref "U1") (pin "33") (pinfunction "USART3-TX/PC4_33") (pintype "bidirectional"))
      (node (ref "U4") (pin "17") (pinfunction "B3_17") (pintype "bidirectional"))
    )
    (net (code "43") (name "PC5") (class "Default")
      (node (ref "U1") (pin "34") (pinfunction "UISART3-RX/PC5_34") (pintype "bidirectional"))
      (node (ref "U4") (pin "16") (pinfunction "B4_16") (pintype "bidirectional"))
    )
    (net (code "44") (name "PD2") (class "Default")
      (node (ref "U1") (pin "83") (pinfunction "PD2_83") (pintype "bidirectional"))
      (node (ref "U2") (pin "1") (pinfunction "~{CS}_1") (pintype "bidirectional"))
    )
    (net (code "45") (name "PE9") (class "Default")
      (node (ref "R15") (pin "1") (pinfunction "P$1_1") (pintype "passive"))
      (node (ref "U1") (pin "40") (pinfunction "PE9_40") (pintype "bidirectional"))
    )
    (net (code "46") (name "PE15") (class "Default")
      (node (ref "R11") (pin "1") (pinfunction "P$1_1") (pintype "passive"))
      (node (ref "U1") (pin "46") (pinfunction "PE15_46") (pintype "bidirectional"))
    )
    (net (code "47") (name "PWRKEY") (class "Default")
      (node (ref "C20") (pin "2") (pinfunction "P$2_2") (pintype "passive"))
      (node (ref "MOD1") (pin "15") (pinfunction "PWRKEY_15") (pintype "input"))
      (node (ref "T1") (pin "3") (pinfunction "C_3") (pintype "passive"))
    )
    (net (code "48") (name "SIM_VDD") (class "Default")
      (node (ref "J1") (pin "C1") (pinfunction "VCC_C1") (pintype "power_in"))
      (node (ref "MOD1") (pin "43") (pinfunction "USIM_VDD_43") (pintype "power_in"))
      (node (ref "R24") (pin "2") (pinfunction "P$2_2") (pintype "passive"))
    )
    (net (code "49") (name "STATUS") (class "Default")
      (node (ref "MOD1") (pin "20") (pinfunction "STATUS_20") (pintype "output"))
      (node (ref "R17") (pin "1") (pinfunction "P$1_1") (pintype "passive"))
    )
    (net (code "50") (name "TGT_NRST") (class "Default")
      (node (ref "CON1") (pin "3") (pinfunction "NRESET_3") (pintype "passive"))
      (node (ref "U1") (pin "14") (pinfunction "NRST_14") (pintype "bidirectional"))
    )
    (net (code "51") (name "TGT_RX") (class "Default")
      (node (ref "TP2") (pin "TP") (pinfunction "TP_TP") (pintype "input"))
      (node (ref "U1") (pin "69") (pinfunction "TGT_RX/PA10_69") (pintype "bidirectional"))
    )
    (net (code "52") (name "TGT_SWCLK") (class "Default")
      (node (ref "CON1") (pin "4") (pinfunction "SWCLK/TCLK_4") (pintype "passive"))
      (node (ref "U1") (pin "76") (pinfunction "SWCLK/PA14_76") (pintype "bidirectional"))
    )
    (net (code "53") (name "TGT_SWDIO") (class "Default")
      (node (ref "CON1") (pin "2") (pinfunction "SWDIO/TMS_2") (pintype "passive"))
      (node (ref "U1") (pin "72") (pinfunction "SWDIO/PA13_72") (pintype "bidirectional"))
    )
    (net (code "54") (name "TGT_SWO") (class "Default")
      (node (ref "CON1") (pin "6") (pinfunction "SWO/TDO_6") (pintype "passive"))
      (node (ref "U1") (pin "89") (pinfunction "SWO/PB3_89") (pintype "bidirectional"))
    )
    (net (code "55") (name "TGT_TX") (class "Default")
      (node (ref "TP1") (pin "TP") (pinfunction "TP_TP") (pintype "input"))
      (node (ref "U1") (pin "68") (pinfunction "TGT_TX/PA9_68") (pintype "bidirectional"))
    )
    (net (code "56") (name "USB_VBUS") (class "Default")
      (node (ref "MOD1") (pin "8") (pinfunction "USB_VBUS_8") (pintype "power_in"))
    )
    (net (code "57") (name "USIM_CLK") (class "Default")
      (node (ref "MOD1") (pin "46") (pinfunction "USIM_CLK_46") (pintype "output"))
      (node (ref "R22") (pin "1") (pinfunction "P$1_1") (pintype "passive"))
    )
    (net (code "58") (name "USIM_DATA") (class "Default")
      (node (ref "MOD1") (pin "45") (pinfunction "USIM_DATA_45") (pintype "bidirectional"))
      (node (ref "R23") (pin "1") (pinfunction "P$1_1") (pintype "passive"))
    )
    (net (code "59") (name "USIM_PRESENCE") (class "Default")
      (node (ref "J1") (pin "DSW2") (pinfunction "DSW2_DSW2") (pintype "output"))
      (node (ref "MOD1") (pin "42") (pinfunction "USIM_PRESENCE_42") (pintype "input"))
      (node (ref "R25") (pin "1") (pinfunction "P$1_1") (pintype "passive"))
    )
    (net (code "60") (name "USIM_RST") (class "Default")
      (node (ref "MOD1") (pin "44") (pinfunction "USIM_RST_44") (pintype "output"))
      (node (ref "R21") (pin "1") (pinfunction "P$1_1") (pintype "passive"))
    )
    (net (code "61") (name "VPP") (class "Default")
      (node (ref "J1") (pin "C6") (pinfunction "VPP_C6") (pintype "power_in"))
    )
    (net (code "62") (name "unconnected-(MOD1-ADC0-Pad24)") (class "Default")
      (node (ref "MOD1") (pin "24") (pinfunction "ADC0_24") (pintype "input"))
    )
    (net (code "63") (name "unconnected-(MOD1-ADC1-Pad2)") (class "Default")
      (node (ref "MOD1") (pin "2") (pinfunction "ADC1_2") (pintype "input"))
    )
    (net (code "64") (name "unconnected-(MOD1-AP_READY-Pad19)") (class "Default")
      (node (ref "MOD1") (pin "19") (pinfunction "AP_READY_19") (pintype "input"))
    )
    (net (code "65") (name "unconnected-(MOD1-CTS-Pad36)") (class "Default")
      (node (ref "MOD1") (pin "36") (pinfunction "CTS_36") (pintype "output"))
    )
    (net (code "66") (name "unconnected-(MOD1-DCD-Pad38)") (class "Default")
      (node (ref "MOD1") (pin "38") (pinfunction "DCD_38") (pintype "output"))
    )
    (net (code "67") (name "unconnected-(MOD1-DTR-Pad30)") (class "Default")
      (node (ref "MOD1") (pin "30") (pinfunction "DTR_30") (pintype "input"))
    )
    (net (code "68") (name "unconnected-(MOD1-GPIO-Pad64)") (class "Default")
      (node (ref "MOD1") (pin "64") (pinfunction "GPIO_64") (pintype "bidirectional"))
    )
    (net (code "69") (name "unconnected-(MOD1-GPIO{slash}SPI_CLK-Pad26)") (class "Default")
      (node (ref "MOD1") (pin "26") (pinfunction "GPIO/SPI_CLK_26") (pintype "output"))
    )
    (net (code "70") (name "unconnected-(MOD1-I2C_SCL-Pad40)") (class "Default")
      (node (ref "MOD1") (pin "40") (pinfunction "I2C_SCL_40") (pintype "input"))
    )
    (net (code "71") (name "unconnected-(MOD1-I2C_SDA-Pad41)") (class "Default")
      (node (ref "MOD1") (pin "41") (pinfunction "I2C_SDA_41") (pintype "bidirectional"))
    )
    (net (code "72") (name "unconnected-(MOD1-I2S_BCLK-Pad4)") (class "Default")
      (node (ref "MOD1") (pin "4") (pinfunction "I2S_BCLK_4") (pintype "output"))
    )
    (net (code "73") (name "unconnected-(MOD1-I2S_D0-Pad6)") (class "Default")
      (node (ref "MOD1") (pin "6") (pinfunction "I2S_D0_6") (pintype "bidirectional"))
    )
    (net (code "74") (name "unconnected-(MOD1-I2S_D1-Pad7)") (class "Default")
      (node (ref "MOD1") (pin "7") (pinfunction "I2S_D1_7") (pintype "bidirectional"))
    )
    (net (code "75") (name "unconnected-(MOD1-I2S_MCLK-Pad63)") (class "Default")
      (node (ref "MOD1") (pin "63") (pinfunction "I2S_MCLK_63") (pintype "output"))
    )
    (net (code "76") (name "unconnected-(MOD1-I2S_WCLK-Pad5)") (class "Default")
      (node (ref "MOD1") (pin "5") (pinfunction "I2S_WCLK_5") (pintype "output"))
    )
    (net (code "77") (name "unconnected-(MOD1-PSM_IND-Pad1)") (class "Default")
      (node (ref "MOD1") (pin "1") (pinfunction "PSM_IND_1") (pintype "output"))
    )
    (net (code "78") (name "unconnected-(MOD1-RESERVED-Pad11)") (class "Default")
      (node (ref "MOD1") (pin "11") (pinfunction "RESERVED_11") (pintype "no_connect"))
    )
    (net (code "79") (name "unconnected-(MOD1-RESERVED-Pad12)") (class "Default")
      (node (ref "MOD1") (pin "12") (pinfunction "RESERVED_12") (pintype "no_connect"))
    )
    (net (code "80") (name "unconnected-(MOD1-RESERVED-Pad13)") (class "Default")
      (node (ref "MOD1") (pin "13") (pinfunction "RESERVED_13") (pintype "no_connect"))
    )
    (net (code "81") (name "unconnected-(MOD1-RESERVED-Pad14)") (class "Default")
      (node (ref "MOD1") (pin "14") (pinfunction "RESERVED_14") (pintype "no_connect"))
    )
    (net (code "82") (name "unconnected-(MOD1-RESERVED-Pad16)") (class "Default")
      (node (ref "MOD1") (pin "16") (pinfunction "RESERVED_16") (pintype "no_connect"))
    )
    (net (code "83") (name "unconnected-(MOD1-RESERVED-Pad25)") (class "Default")
      (node (ref "MOD1") (pin "25") (pinfunction "RESERVED_25") (pintype "no_connect"))
    )
    (net (code "84") (name "unconnected-(MOD1-RESERVED-Pad51)") (class "Default")
      (node (ref "MOD1") (pin "51") (pinfunction "RESERVED_51") (pintype "no_connect"))
    )
    (net (code "85") (name "unconnected-(MOD1-RESERVED-Pad56)") (class "Default")
      (node (ref "MOD1") (pin "56") (pinfunction "RESERVED_56") (pintype "no_connect"))
    )
    (net (code "86") (name "unconnected-(MOD1-RESERVED-Pad57)") (class "Default")
      (node (ref "MOD1") (pin "57") (pinfunction "RESERVED_57") (pintype "no_connect"))
    )
    (net (code "87") (name "unconnected-(MOD1-RESERVED-Pad65)") (class "Default")
      (node (ref "MOD1") (pin "65") (pinfunction "RESERVED_65") (pintype "no_connect"))
    )
    (net (code "88") (name "unconnected-(MOD1-RESERVED-Pad66)") (class "Default")
      (node (ref "MOD1") (pin "66") (pinfunction "RESERVED_66") (pintype "no_connect"))
    )
    (net (code "89") (name "unconnected-(MOD1-RESERVED-Pad76)") (class "Default")
      (node (ref "MOD1") (pin "76") (pinfunction "RESERVED_76") (pintype "no_connect"))
    )
    (net (code "90") (name "unconnected-(MOD1-RESERVED-Pad77)") (class "Default")
      (node (ref "MOD1") (pin "77") (pinfunction "RESERVED_77") (pintype "no_connect"))
    )
    (net (code "91") (name "unconnected-(MOD1-RESERVED-Pad78)") (class "Default")
      (node (ref "MOD1") (pin "78") (pinfunction "RESERVED_78") (pintype "no_connect"))
    )
    (net (code "92") (name "unconnected-(MOD1-RESERVED-Pad83)") (class "Default")
      (node (ref "MOD1") (pin "83") (pinfunction "RESERVED_83") (pintype "no_connect"))
    )
    (net (code "93") (name "unconnected-(MOD1-RESERVED-Pad84)") (class "Default")
      (node (ref "MOD1") (pin "84") (pinfunction "RESERVED_84") (pintype "no_connect"))
    )
    (net (code "94") (name "unconnected-(MOD1-RESERVED-Pad85)") (class "Default")
      (node (ref "MOD1") (pin "85") (pinfunction "RESERVED_85") (pintype "no_connect"))
    )
    (net (code "95") (name "unconnected-(MOD1-RESERVED-Pad86)") (class "Default")
      (node (ref "MOD1") (pin "86") (pinfunction "RESERVED_86") (pintype "no_connect"))
    )
    (net (code "96") (name "unconnected-(MOD1-RESERVED-Pad87)") (class "Default")
      (node (ref "MOD1") (pin "87") (pinfunction "RESERVED_87") (pintype "no_connect"))
    )
    (net (code "97") (name "unconnected-(MOD1-RESERVED-Pad88)") (class "Default")
      (node (ref "MOD1") (pin "88") (pinfunction "RESERVED_88") (pintype "no_connect"))
    )
    (net (code "98") (name "unconnected-(MOD1-RESERVED-Pad92)") (class "Default")
      (node (ref "MOD1") (pin "92") (pinfunction "RESERVED_92") (pintype "no_connect"))
    )
    (net (code "99") (name "unconnected-(MOD1-RESERVED-Pad93)") (class "Default")
      (node (ref "MOD1") (pin "93") (pinfunction "RESERVED_93") (pintype "no_connect"))
    )
    (net (code "100") (name "unconnected-(MOD1-RESERVED-Pad94)") (class "Default")
      (node (ref "MOD1") (pin "94") (pinfunction "RESERVED_94") (pintype "no_connect"))
    )
    (net (code "101") (name "unconnected-(MOD1-RESERVED-Pad95)") (class "Default")
      (node (ref "MOD1") (pin "95") (pinfunction "RESERVED_95") (pintype "no_connect"))
    )
    (net (code "102") (name "unconnected-(MOD1-RESERVED-Pad96)") (class "Default")
      (node (ref "MOD1") (pin "96") (pinfunction "RESERVED_96") (pintype "no_connect"))
    )
    (net (code "103") (name "unconnected-(MOD1-RESERVED-Pad97)") (class "Default")
      (node (ref "MOD1") (pin "97") (pinfunction "RESERVED_97") (pintype "no_connect"))
    )
    (net (code "104") (name "unconnected-(MOD1-RESERVED-Pad98)") (class "Default")
      (node (ref "MOD1") (pin "98") (pinfunction "RESERVED_98") (pintype "no_connect"))
    )
    (net (code "105") (name "unconnected-(MOD1-RESERVED-Pad99)") (class "Default")
      (node (ref "MOD1") (pin "99") (pinfunction "RESERVED_99") (pintype "no_connect"))
    )
    (net (code "106") (name "unconnected-(MOD1-RI-Pad39)") (class "Default")
      (node (ref "MOD1") (pin "39") (pinfunction "RI_39") (pintype "output"))
    )
    (net (code "107") (name "unconnected-(MOD1-RTS-Pad37)") (class "Default")
      (node (ref "MOD1") (pin "37") (pinfunction "RTS_37") (pintype "input"))
    )
    (net (code "108") (name "unconnected-(MOD1-UART3_RXD{slash}SPI_MISO-Pad28)") (class "Default")
      (node (ref "MOD1") (pin "28") (pinfunction "UART3_RXD/SPI_MISO_28") (pintype "input"))
    )
    (net (code "109") (name "unconnected-(MOD1-UART3_TXD{slash}SPI_MOSI-Pad27)") (class "Default")
      (node (ref "MOD1") (pin "27") (pinfunction "UART3_TXD/SPI_MOSI_27") (pintype "output"))
    )
    (net (code "110") (name "unconnected-(MOD1-USB_BOOT-Pad75)") (class "Default")
      (node (ref "MOD1") (pin "75") (pinfunction "USB_BOOT_75") (pintype "input"))
    )
    (net (code "111") (name "unconnected-(MOD1-USB_DM-Pad10)") (class "Default")
      (node (ref "MOD1") (pin "10") (pinfunction "USB_DM_10") (pintype "bidirectional"))
    )
    (net (code "112") (name "unconnected-(MOD1-USB_DP-Pad9)") (class "Default")
      (node (ref "MOD1") (pin "9") (pinfunction "USB_DP_9") (pintype "bidirectional"))
    )
    (net (code "113") (name "unconnected-(MOD1-W_DISABLE#-Pad18)") (class "Default")
      (node (ref "MOD1") (pin "18") (pinfunction "W_DISABLE#_18") (pintype "input"))
    )
    (net (code "114") (name "unconnected-(U1A-AIN5{slash}PA0-Pad23)") (class "Default")
      (node (ref "U1") (pin "23") (pinfunction "AIN5/PA0_23") (pintype "bidirectional"))
    )
    (net (code "115") (name "unconnected-(U1A-AIN6{slash}PA1-Pad24)") (class "Default")
      (node (ref "U1") (pin "24") (pinfunction "AIN6/PA1_24") (pintype "bidirectional"))
    )
    (net (code "116") (name "unconnected-(U1A-AIN15{slash}PB0-Pad35)") (class "Default")
      (node (ref "U1") (pin "35") (pinfunction "AIN15/PB0_35") (pintype "bidirectional"))
    )
    (net (code "117") (name "unconnected-(U1A-AIN16{slash}PB1-Pad36)") (class "Default")
      (node (ref "U1") (pin "36") (pinfunction "AIN16/PB1_36") (pintype "bidirectional"))
    )
    (net (code "118") (name "unconnected-(U1A-MISO2{slash}PC2-Pad17)") (class "Default")
      (node (ref "U1") (pin "17") (pinfunction "MISO2/PC2_17") (pintype "bidirectional"))
    )
    (net (code "119") (name "unconnected-(U1A-MOSI1{slash}PA7-Pad32)") (class "Default")
      (node (ref "U1") (pin "32") (pinfunction "MOSI1/PA7_32") (pintype "bidirectional"))
    )
    (net (code "120") (name "unconnected-(U1A-MOSI2{slash}PC3-Pad18)") (class "Default")
      (node (ref "U1") (pin "18") (pinfunction "MOSI2/PC3_18") (pintype "bidirectional"))
    )
    (net (code "121") (name "unconnected-(U1A-NSS2{slash}PB12-Pad51)") (class "Default")
      (node (ref "U1") (pin "51") (pinfunction "NSS2/PB12_51") (pintype "bidirectional"))
    )
    (net (code "122") (name "unconnected-(U1A-PA8-Pad67)") (class "Default")
      (node (ref "U1") (pin "67") (pinfunction "PA8_67") (pintype "bidirectional"))
    )
    (net (code "123") (name "unconnected-(U1A-SCK2{slash}PB13-Pad52)") (class "Default")
      (node (ref "U1") (pin "52") (pinfunction "SCK2/PB13_52") (pintype "bidirectional"))
    )
    (net (code "124") (name "unconnected-(U1A-SCL1{slash}PB8-Pad95)") (class "Default")
      (node (ref "U1") (pin "95") (pinfunction "SCL1/PB8_95") (pintype "bidirectional"))
    )
    (net (code "125") (name "unconnected-(U1A-SCL2{slash}PB10-Pad47)") (class "Default")
      (node (ref "U1") (pin "47") (pinfunction "SCL2/PB10_47") (pintype "bidirectional"))
    )
    (net (code "126") (name "unconnected-(U1A-SDA2{slash}PB11-Pad48)") (class "Default")
      (node (ref "U1") (pin "48") (pinfunction "SDA2/PB11_48") (pintype "bidirectional"))
    )
    (net (code "127") (name "unconnected-(U1B-PA11-Pad70)") (class "Default")
      (node (ref "U1") (pin "70") (pinfunction "PA11_70") (pintype "bidirectional"))
    )
    (net (code "128") (name "unconnected-(U1B-PA12-Pad71)") (class "Default")
      (node (ref "U1") (pin "71") (pinfunction "PA12_71") (pintype "bidirectional"))
    )
    (net (code "129") (name "unconnected-(U1B-PB2-Pad37)") (class "Default")
      (node (ref "U1") (pin "37") (pinfunction "PB2_37") (pintype "bidirectional"))
    )
    (net (code "130") (name "unconnected-(U1B-PB4-Pad90)") (class "Default")
      (node (ref "U1") (pin "90") (pinfunction "PB4_90") (pintype "bidirectional"))
    )
    (net (code "131") (name "unconnected-(U1B-PC6-Pad63)") (class "Default")
      (node (ref "U1") (pin "63") (pinfunction "PC6_63") (pintype "bidirectional"))
    )
    (net (code "132") (name "unconnected-(U1B-PC7-Pad64)") (class "Default")
      (node (ref "U1") (pin "64") (pinfunction "PC7_64") (pintype "bidirectional"))
    )
    (net (code "133") (name "unconnected-(U1B-PC8-Pad65)") (class "Default")
      (node (ref "U1") (pin "65") (pinfunction "PC8_65") (pintype "bidirectional"))
    )
    (net (code "134") (name "unconnected-(U1B-PC13-Pad7)") (class "Default")
      (node (ref "U1") (pin "7") (pinfunction "PC13_7") (pintype "bidirectional"))
    )
    (net (code "135") (name "unconnected-(U1B-PD4-Pad85)") (class "Default")
      (node (ref "U1") (pin "85") (pinfunction "PD4_85") (pintype "bidirectional"))
    )
    (net (code "136") (name "unconnected-(U1B-PD5-Pad86)") (class "Default")
      (node (ref "U1") (pin "86") (pinfunction "PD5_86") (pintype "bidirectional"))
    )
    (net (code "137") (name "unconnected-(U1B-PD6-Pad87)") (class "Default")
      (node (ref "U1") (pin "87") (pinfunction "PD6_87") (pintype "bidirectional"))
    )
    (net (code "138") (name "unconnected-(U1B-PD7-Pad88)") (class "Default")
      (node (ref "U1") (pin "88") (pinfunction "PD7_88") (pintype "bidirectional"))
    )
    (net (code "139") (name "unconnected-(U1B-PD8-Pad55)") (class "Default")
      (node (ref "U1") (pin "55") (pinfunction "PD8_55") (pintype "bidirectional"))
    )
    (net (code "140") (name "unconnected-(U1B-PD9-Pad56)") (class "Default")
      (node (ref "U1") (pin "56") (pinfunction "PD9_56") (pintype "bidirectional"))
    )
    (net (code "141") (name "unconnected-(U1B-PD10-Pad57)") (class "Default")
      (node (ref "U1") (pin "57") (pinfunction "PD10_57") (pintype "bidirectional"))
    )
    (net (code "142") (name "unconnected-(U1B-PD11-Pad58)") (class "Default")
      (node (ref "U1") (pin "58") (pinfunction "PD11_58") (pintype "bidirectional"))
    )
    (net (code "143") (name "unconnected-(U1B-PD12-Pad59)") (class "Default")
      (node (ref "U1") (pin "59") (pinfunction "PD12_59") (pintype "bidirectional"))
    )
    (net (code "144") (name "unconnected-(U1B-PD13-Pad60)") (class "Default")
      (node (ref "U1") (pin "60") (pinfunction "PD13_60") (pintype "bidirectional"))
    )
    (net (code "145") (name "unconnected-(U1B-PD14-Pad61)") (class "Default")
      (node (ref "U1") (pin "61") (pinfunction "PD14_61") (pintype "bidirectional"))
    )
    (net (code "146") (name "unconnected-(U1B-PD15-Pad62)") (class "Default")
      (node (ref "U1") (pin "62") (pinfunction "PD15_62") (pintype "bidirectional"))
    )
    (net (code "147") (name "unconnected-(U1B-PE2-Pad1)") (class "Default")
      (node (ref "U1") (pin "1") (pinfunction "PE2_1") (pintype "bidirectional"))
    )
    (net (code "148") (name "unconnected-(U1B-PE3-Pad2)") (class "Default")
      (node (ref "U1") (pin "2") (pinfunction "PE3_2") (pintype "bidirectional"))
    )
    (net (code "149") (name "unconnected-(U1B-PE4-Pad3)") (class "Default")
      (node (ref "U1") (pin "3") (pinfunction "PE4_3") (pintype "bidirectional"))
    )
    (net (code "150") (name "unconnected-(U1B-PE10-Pad41)") (class "Default")
      (node (ref "U1") (pin "41") (pinfunction "PE10_41") (pintype "bidirectional"))
    )
    (net (code "151") (name "unconnected-(U1B-PE13-Pad44)") (class "Default")
      (node (ref "U1") (pin "44") (pinfunction "PE13_44") (pintype "bidirectional"))
    )
    (net (code "152") (name "unconnected-(U1B-PE14-Pad45)") (class "Default")
      (node (ref "U1") (pin "45") (pinfunction "PE14_45") (pintype "bidirectional"))
    )
    (net (code "153") (name "unconnected-(U1C-MISO2{slash}PB14-Pad53)") (class "Default")
      (node (ref "U1") (pin "53") (pinfunction "MISO2/PB14_53") (pintype "bidirectional"))
    )
    (net (code "154") (name "unconnected-(U1C-MISO3{slash}PC11-Pad79)") (class "Default")
      (node (ref "U1") (pin "79") (pinfunction "MISO3/PC11_79") (pintype "bidirectional"))
    )
    (net (code "155") (name "unconnected-(U1C-MOSI2{slash}PB15-Pad54)") (class "Default")
      (node (ref "U1") (pin "54") (pinfunction "MOSI2/PB15_54") (pintype "bidirectional"))
    )
    (net (code "156") (name "unconnected-(U1C-MOSI3{slash}PC12-Pad80)") (class "Default")
      (node (ref "U1") (pin "80") (pinfunction "MOSI3/PC12_80") (pintype "bidirectional"))
    )
    (net (code "157") (name "unconnected-(U1C-NSS1{slash}PA15-Pad77)") (class "Default")
      (node (ref "U1") (pin "77") (pinfunction "NSS1/PA15_77") (pintype "bidirectional"))
    )
    (net (code "158") (name "unconnected-(U1C-NSS2{slash}SDA1{slash}PB9-Pad96)") (class "Default")
      (node (ref "U1") (pin "96") (pinfunction "NSS2/SDA1/PB9_96") (pintype "bidirectional"))
    )
    (net (code "159") (name "unconnected-(U1C-NSS3{slash}PA4-Pad29)") (class "Default")
      (node (ref "U1") (pin "29") (pinfunction "NSS3/PA4_29") (pintype "bidirectional"))
    )
    (net (code "160") (name "unconnected-(U1C-PC9-Pad66)") (class "Default")
      (node (ref "U1") (pin "66") (pinfunction "PC9_66") (pintype "bidirectional"))
    )
    (net (code "161") (name "unconnected-(U1C-PD0-Pad81)") (class "Default")
      (node (ref "U1") (pin "81") (pinfunction "PD0_81") (pintype "bidirectional"))
    )
    (net (code "162") (name "unconnected-(U1C-PD1-Pad82)") (class "Default")
      (node (ref "U1") (pin "82") (pinfunction "PD1_82") (pintype "bidirectional"))
    )
    (net (code "163") (name "unconnected-(U1C-PE0-Pad97)") (class "Default")
      (node (ref "U1") (pin "97") (pinfunction "PE0_97") (pintype "bidirectional"))
    )
    (net (code "164") (name "unconnected-(U1C-PE1-Pad98)") (class "Default")
      (node (ref "U1") (pin "98") (pinfunction "PE1_98") (pintype "bidirectional"))
    )
    (net (code "165") (name "unconnected-(U1C-PE5-Pad4)") (class "Default")
      (node (ref "U1") (pin "4") (pinfunction "PE5_4") (pintype "bidirectional"))
    )
    (net (code "166") (name "unconnected-(U1C-PE6-Pad5)") (class "Default")
      (node (ref "U1") (pin "5") (pinfunction "PE6_5") (pintype "bidirectional"))
    )
    (net (code "167") (name "unconnected-(U1C-PE7-Pad38)") (class "Default")
      (node (ref "U1") (pin "38") (pinfunction "PE7_38") (pintype "bidirectional"))
    )
    (net (code "168") (name "unconnected-(U1C-PE8-Pad39)") (class "Default")
      (node (ref "U1") (pin "39") (pinfunction "PE8_39") (pintype "bidirectional"))
    )
    (net (code "169") (name "unconnected-(U1C-PE11-Pad42)") (class "Default")
      (node (ref "U1") (pin "42") (pinfunction "PE11_42") (pintype "bidirectional"))
    )
    (net (code "170") (name "unconnected-(U1C-PE12-Pad43)") (class "Default")
      (node (ref "U1") (pin "43") (pinfunction "PE12_43") (pintype "bidirectional"))
    )
    (net (code "171") (name "unconnected-(U1C-SCK2{slash}PD3-Pad84)") (class "Default")
      (node (ref "U1") (pin "84") (pinfunction "SCK2/PD3_84") (pintype "bidirectional"))
    )
    (net (code "172") (name "unconnected-(U1C-SCK3{slash}PC10-Pad78)") (class "Default")
      (node (ref "U1") (pin "78") (pinfunction "SCK3/PC10_78") (pintype "bidirectional"))
    )
    (net (code "173") (name "unconnected-(U3-NC1-Pad1)") (class "Default")
      (node (ref "U3") (pin "1") (pinfunction "NC1_1") (pintype "bidirectional"))
    )
    (net (code "174") (name "unconnected-(U3-NC2-Pad2)") (class "Default")
      (node (ref "U3") (pin "2") (pinfunction "NC2_2") (pintype "bidirectional"))
    )
    (net (code "175") (name "unconnected-(U3-NC3-Pad3)") (class "Default")
      (node (ref "U3") (pin "3") (pinfunction "NC3_3") (pintype "bidirectional"))
    )
    (net (code "176") (name "unconnected-(U3-NC7-Pad7)") (class "Default")
      (node (ref "U3") (pin "7") (pinfunction "NC7_7") (pintype "bidirectional"))
    )
    (net (code "177") (name "unconnected-(U4-A5-Pad6)") (class "Default")
      (node (ref "U4") (pin "6") (pinfunction "A5_6") (pintype "bidirectional"))
    )
    (net (code "178") (name "unconnected-(U4-A6-Pad7)") (class "Default")
      (node (ref "U4") (pin "7") (pinfunction "A6_7") (pintype "bidirectional"))
    )
    (net (code "179") (name "unconnected-(U4-A7-Pad8)") (class "Default")
      (node (ref "U4") (pin "8") (pinfunction "A7_8") (pintype "bidirectional"))
    )
    (net (code "180") (name "unconnected-(U4-A8-Pad9)") (class "Default")
      (node (ref "U4") (pin "9") (pinfunction "A8_9") (pintype "bidirectional"))
    )
    (net (code "181") (name "unconnected-(U4-B5-Pad15)") (class "Default")
      (node (ref "U4") (pin "15") (pinfunction "B5_15") (pintype "bidirectional"))
    )
    (net (code "182") (name "unconnected-(U4-B6-Pad14)") (class "Default")
      (node (ref "U4") (pin "14") (pinfunction "B6_14") (pintype "bidirectional"))
    )
    (net (code "183") (name "unconnected-(U4-B7-Pad13)") (class "Default")
      (node (ref "U4") (pin "13") (pinfunction "B7_13") (pintype "bidirectional"))
    )
    (net (code "184") (name "unconnected-(U4-B8-Pad12)") (class "Default")
      (node (ref "U4") (pin "12") (pinfunction "B8_12") (pintype "bidirectional"))
    )
  )
)
